# Schematic.net
KiCad netlist of a schematic drawn in EAGLE
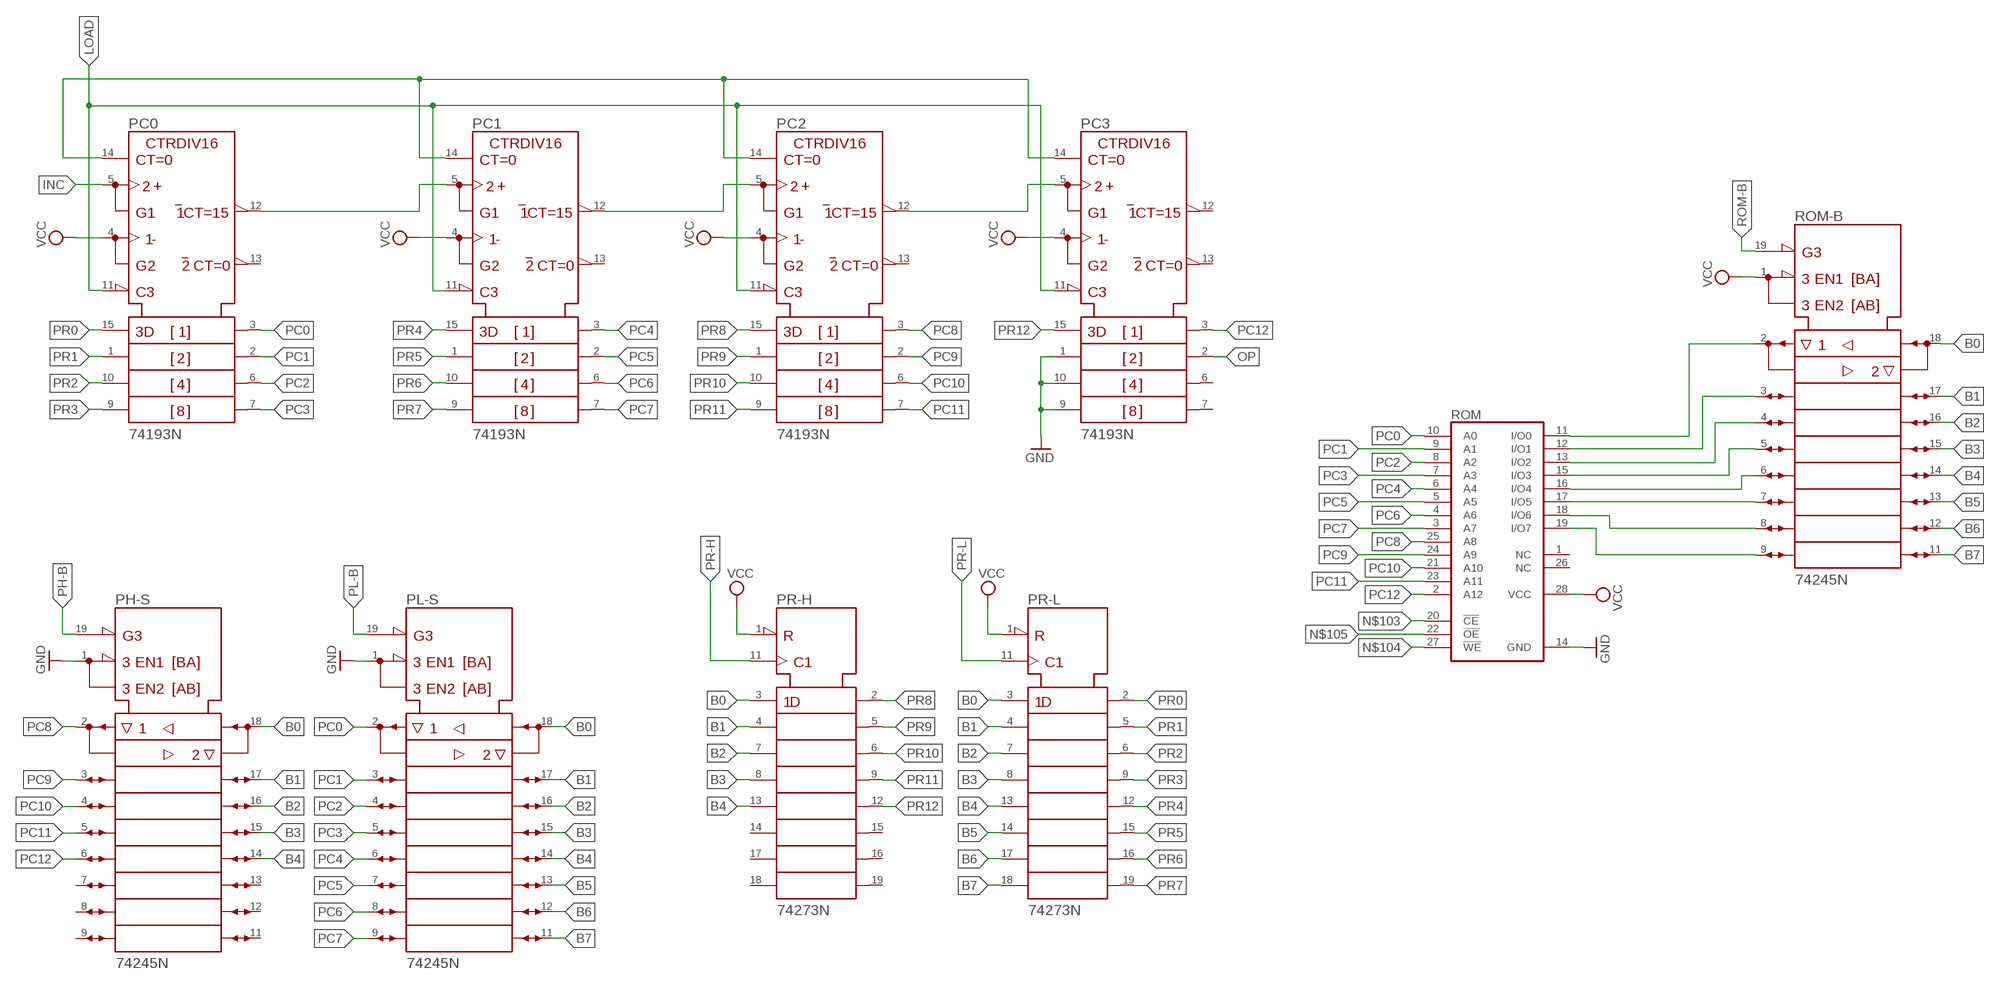
[diagram p0: schematic, sheet 1, part 1 of 3]
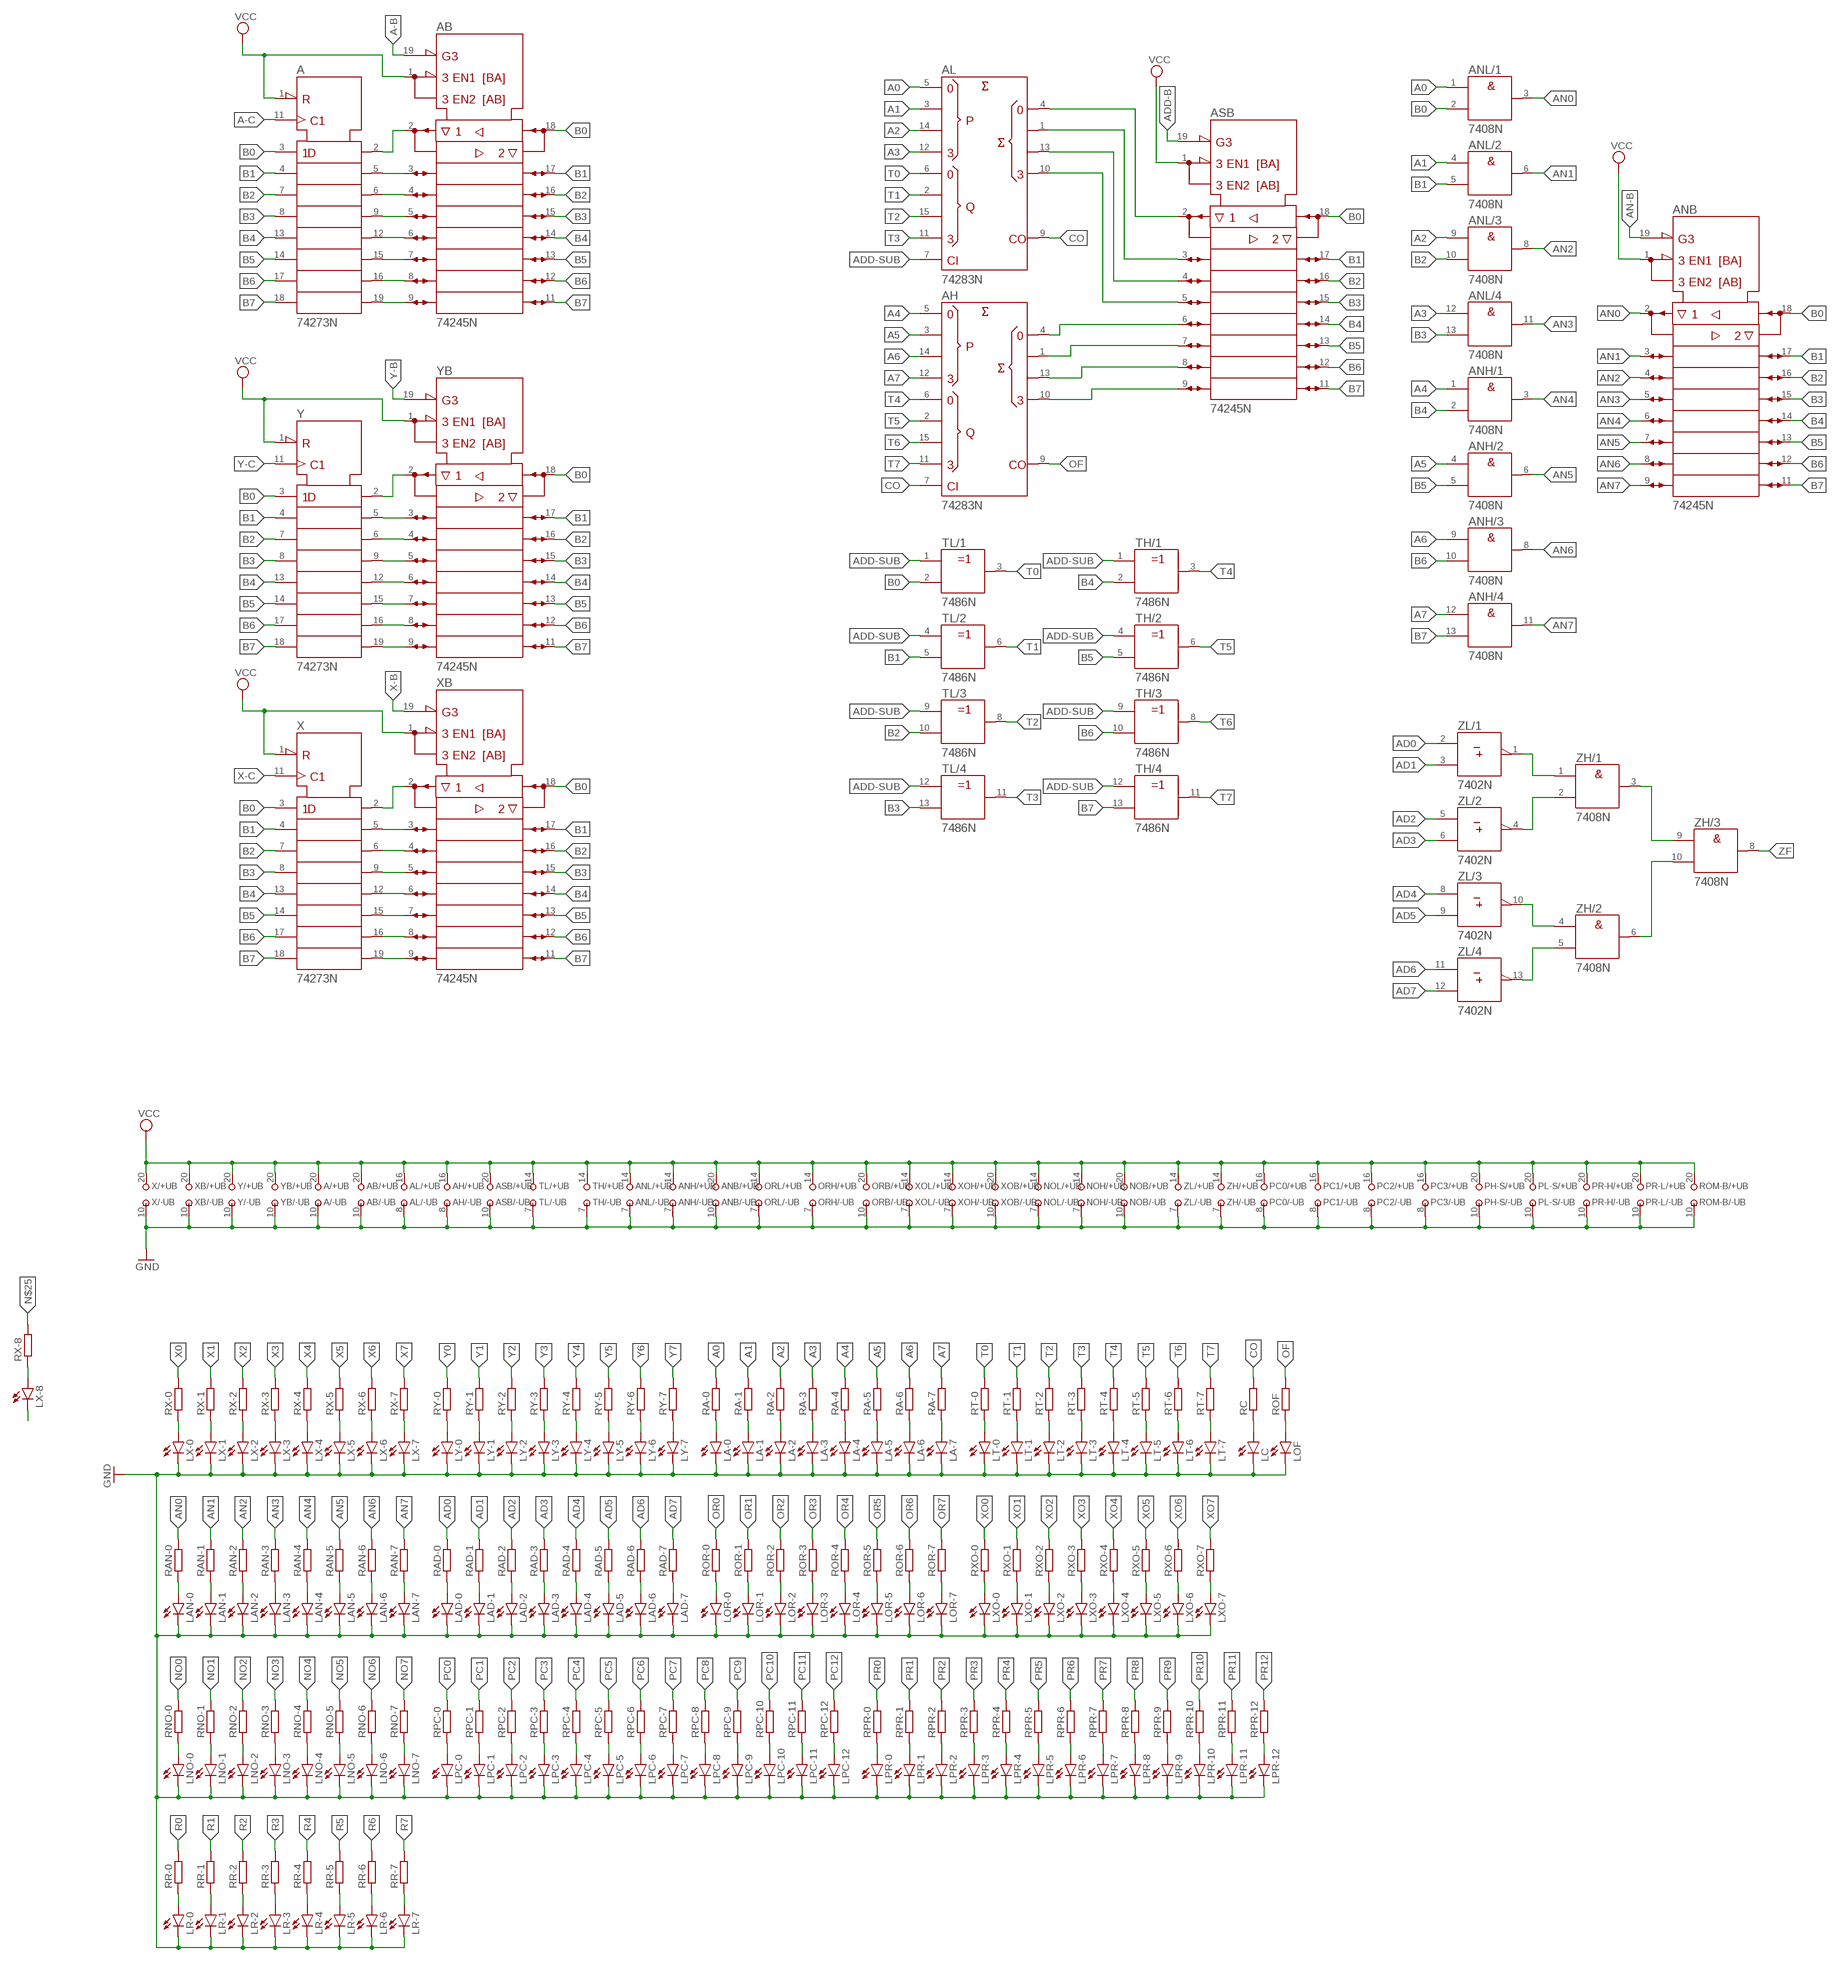
[diagram p1: schematic, sheet 1, part 2 of 3]
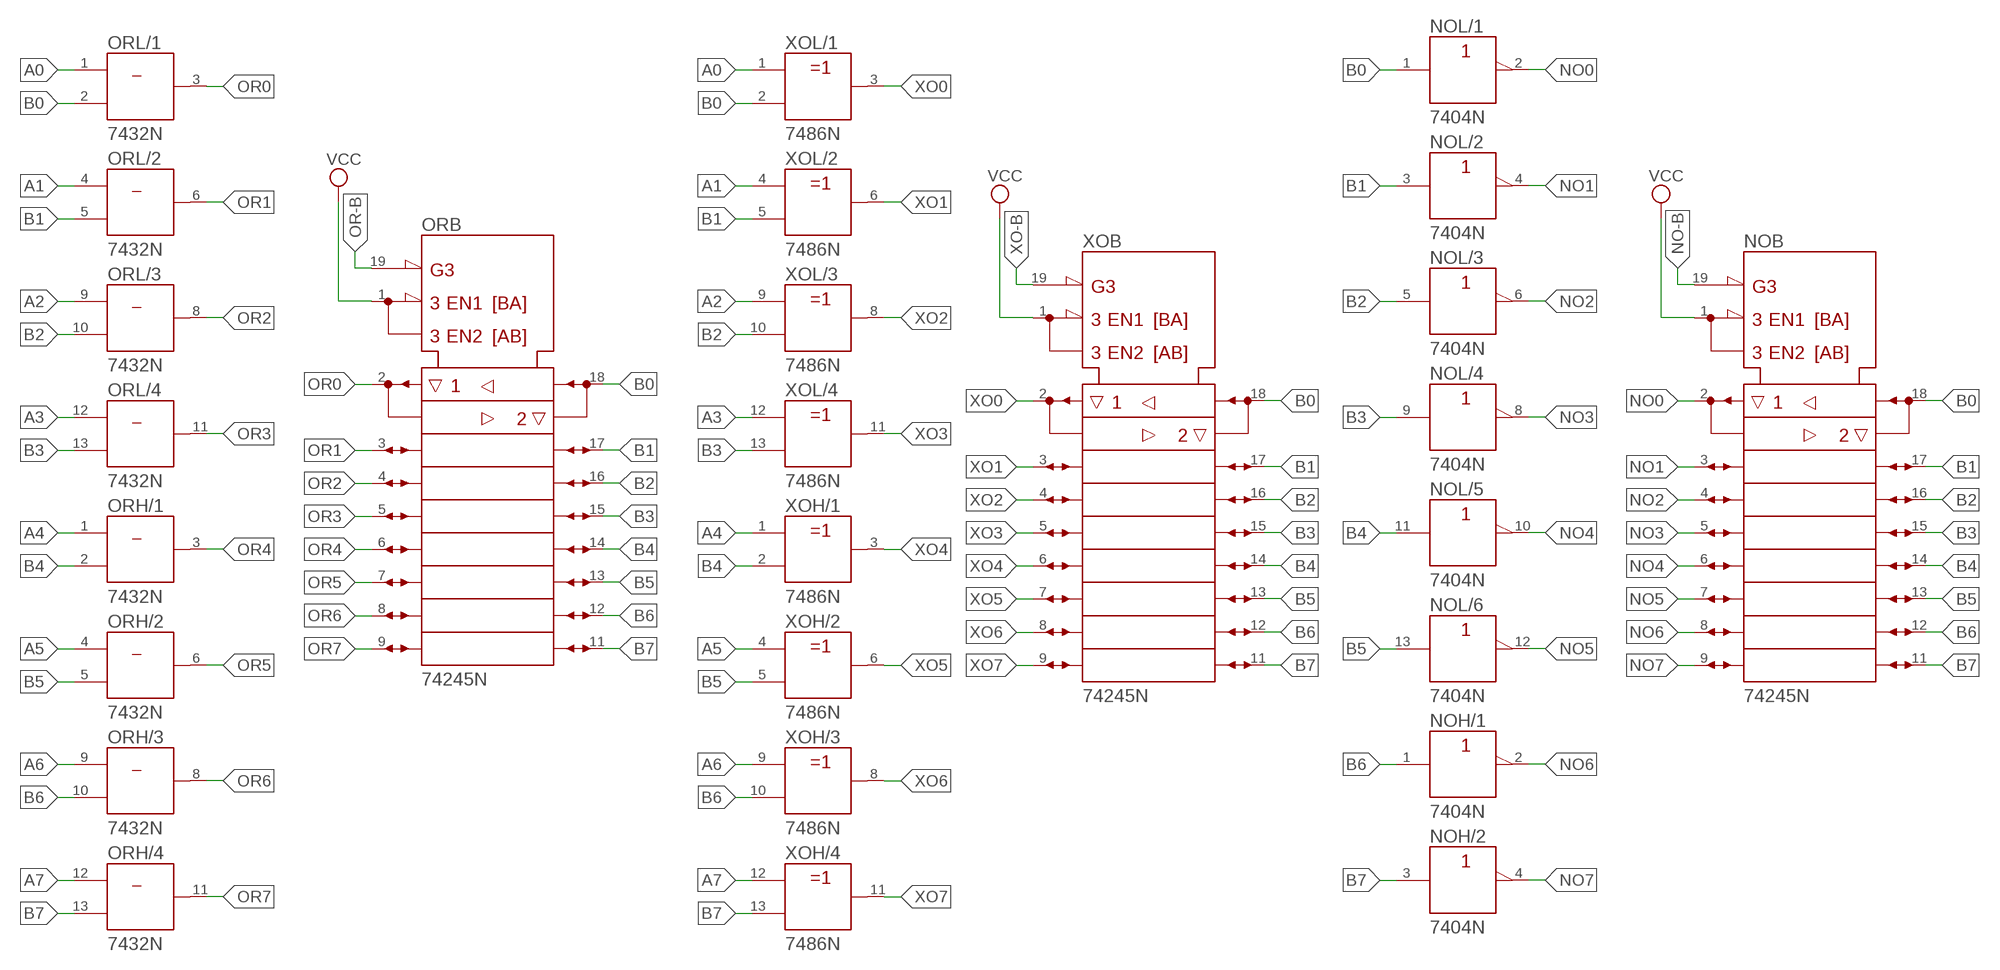
[diagram p2: schematic, sheet 1, part 3 of 3]

(export (version "E")
  (design (tool "Eeschema 10.0.6"))
  (components
    (comp (ref "A")
      (value "74273N")
      (footprint "eagle-import:DIL20")
      (libsource (lib "eagle-import") (part "74273N"))
    )
    (comp (ref "AB")
      (value "74245N")
      (footprint "eagle-import:DIL20")
      (libsource (lib "eagle-import") (part "74245N"))
    )
    (comp (ref "AH")
      (value "74283N")
      (footprint "eagle-import:DIL16")
      (libsource (lib "eagle-import") (part "74283N"))
    )
    (comp (ref "AL")
      (value "74283N")
      (footprint "eagle-import:DIL16")
      (libsource (lib "eagle-import") (part "74283N"))
    )
    (comp (ref "ANB")
      (value "74245N")
      (footprint "eagle-import:DIL20")
      (libsource (lib "eagle-import") (part "74245N"))
    )
    (comp (ref "ANH")
      (value "7408N")
      (footprint "eagle-import:DIL14")
      (libsource (lib "eagle-import") (part "7408N"))
    )
    (comp (ref "ANL")
      (value "7408N")
      (footprint "eagle-import:DIL14")
      (libsource (lib "eagle-import") (part "7408N"))
    )
    (comp (ref "ASB")
      (value "74245N")
      (footprint "eagle-import:DIL20")
      (libsource (lib "eagle-import") (part "74245N"))
    )
    (comp (ref "LA-0")
      (value "LED5MM")
      (footprint "eagle-import:LED5MM")
      (libsource (lib "eagle-import") (part "LED5MM"))
    )
    (comp (ref "LA-1")
      (value "LED5MM")
      (footprint "eagle-import:LED5MM")
      (libsource (lib "eagle-import") (part "LED5MM"))
    )
    (comp (ref "LA-2")
      (value "LED5MM")
      (footprint "eagle-import:LED5MM")
      (libsource (lib "eagle-import") (part "LED5MM"))
    )
    (comp (ref "LA-3")
      (value "LED5MM")
      (footprint "eagle-import:LED5MM")
      (libsource (lib "eagle-import") (part "LED5MM"))
    )
    (comp (ref "LA-4")
      (value "LED5MM")
      (footprint "eagle-import:LED5MM")
      (libsource (lib "eagle-import") (part "LED5MM"))
    )
    (comp (ref "LA-5")
      (value "LED5MM")
      (footprint "eagle-import:LED5MM")
      (libsource (lib "eagle-import") (part "LED5MM"))
    )
    (comp (ref "LA-6")
      (value "LED5MM")
      (footprint "eagle-import:LED5MM")
      (libsource (lib "eagle-import") (part "LED5MM"))
    )
    (comp (ref "LA-7")
      (value "LED5MM")
      (footprint "eagle-import:LED5MM")
      (libsource (lib "eagle-import") (part "LED5MM"))
    )
    (comp (ref "LAD-0")
      (value "LED5MM")
      (footprint "eagle-import:LED5MM")
      (libsource (lib "eagle-import") (part "LED5MM"))
    )
    (comp (ref "LAD-1")
      (value "LED5MM")
      (footprint "eagle-import:LED5MM")
      (libsource (lib "eagle-import") (part "LED5MM"))
    )
    (comp (ref "LAD-2")
      (value "LED5MM")
      (footprint "eagle-import:LED5MM")
      (libsource (lib "eagle-import") (part "LED5MM"))
    )
    (comp (ref "LAD-3")
      (value "LED5MM")
      (footprint "eagle-import:LED5MM")
      (libsource (lib "eagle-import") (part "LED5MM"))
    )
    (comp (ref "LAD-4")
      (value "LED5MM")
      (footprint "eagle-import:LED5MM")
      (libsource (lib "eagle-import") (part "LED5MM"))
    )
    (comp (ref "LAD-5")
      (value "LED5MM")
      (footprint "eagle-import:LED5MM")
      (libsource (lib "eagle-import") (part "LED5MM"))
    )
    (comp (ref "LAD-6")
      (value "LED5MM")
      (footprint "eagle-import:LED5MM")
      (libsource (lib "eagle-import") (part "LED5MM"))
    )
    (comp (ref "LAD-7")
      (value "LED5MM")
      (footprint "eagle-import:LED5MM")
      (libsource (lib "eagle-import") (part "LED5MM"))
    )
    (comp (ref "LAN-0")
      (value "LED5MM")
      (footprint "eagle-import:LED5MM")
      (libsource (lib "eagle-import") (part "LED5MM"))
    )
    (comp (ref "LAN-1")
      (value "LED5MM")
      (footprint "eagle-import:LED5MM")
      (libsource (lib "eagle-import") (part "LED5MM"))
    )
    (comp (ref "LAN-2")
      (value "LED5MM")
      (footprint "eagle-import:LED5MM")
      (libsource (lib "eagle-import") (part "LED5MM"))
    )
    (comp (ref "LAN-3")
      (value "LED5MM")
      (footprint "eagle-import:LED5MM")
      (libsource (lib "eagle-import") (part "LED5MM"))
    )
    (comp (ref "LAN-4")
      (value "LED5MM")
      (footprint "eagle-import:LED5MM")
      (libsource (lib "eagle-import") (part "LED5MM"))
    )
    (comp (ref "LAN-5")
      (value "LED5MM")
      (footprint "eagle-import:LED5MM")
      (libsource (lib "eagle-import") (part "LED5MM"))
    )
    (comp (ref "LAN-6")
      (value "LED5MM")
      (footprint "eagle-import:LED5MM")
      (libsource (lib "eagle-import") (part "LED5MM"))
    )
    (comp (ref "LAN-7")
      (value "LED5MM")
      (footprint "eagle-import:LED5MM")
      (libsource (lib "eagle-import") (part "LED5MM"))
    )
    (comp (ref "LC")
      (value "LED5MM")
      (footprint "eagle-import:LED5MM")
      (libsource (lib "eagle-import") (part "LED5MM"))
    )
    (comp (ref "LNO-0")
      (value "LED5MM")
      (footprint "eagle-import:LED5MM")
      (libsource (lib "eagle-import") (part "LED5MM"))
    )
    (comp (ref "LNO-1")
      (value "LED5MM")
      (footprint "eagle-import:LED5MM")
      (libsource (lib "eagle-import") (part "LED5MM"))
    )
    (comp (ref "LNO-2")
      (value "LED5MM")
      (footprint "eagle-import:LED5MM")
      (libsource (lib "eagle-import") (part "LED5MM"))
    )
    (comp (ref "LNO-3")
      (value "LED5MM")
      (footprint "eagle-import:LED5MM")
      (libsource (lib "eagle-import") (part "LED5MM"))
    )
    (comp (ref "LNO-4")
      (value "LED5MM")
      (footprint "eagle-import:LED5MM")
      (libsource (lib "eagle-import") (part "LED5MM"))
    )
    (comp (ref "LNO-5")
      (value "LED5MM")
      (footprint "eagle-import:LED5MM")
      (libsource (lib "eagle-import") (part "LED5MM"))
    )
    (comp (ref "LNO-6")
      (value "LED5MM")
      (footprint "eagle-import:LED5MM")
      (libsource (lib "eagle-import") (part "LED5MM"))
    )
    (comp (ref "LNO-7")
      (value "LED5MM")
      (footprint "eagle-import:LED5MM")
      (libsource (lib "eagle-import") (part "LED5MM"))
    )
    (comp (ref "LOF")
      (value "LED5MM")
      (footprint "eagle-import:LED5MM")
      (libsource (lib "eagle-import") (part "LED5MM"))
    )
    (comp (ref "LOR-0")
      (value "LED5MM")
      (footprint "eagle-import:LED5MM")
      (libsource (lib "eagle-import") (part "LED5MM"))
    )
    (comp (ref "LOR-1")
      (value "LED5MM")
      (footprint "eagle-import:LED5MM")
      (libsource (lib "eagle-import") (part "LED5MM"))
    )
    (comp (ref "LOR-2")
      (value "LED5MM")
      (footprint "eagle-import:LED5MM")
      (libsource (lib "eagle-import") (part "LED5MM"))
    )
    (comp (ref "LOR-3")
      (value "LED5MM")
      (footprint "eagle-import:LED5MM")
      (libsource (lib "eagle-import") (part "LED5MM"))
    )
    (comp (ref "LOR-4")
      (value "LED5MM")
      (footprint "eagle-import:LED5MM")
      (libsource (lib "eagle-import") (part "LED5MM"))
    )
    (comp (ref "LOR-5")
      (value "LED5MM")
      (footprint "eagle-import:LED5MM")
      (libsource (lib "eagle-import") (part "LED5MM"))
    )
    (comp (ref "LOR-6")
      (value "LED5MM")
      (footprint "eagle-import:LED5MM")
      (libsource (lib "eagle-import") (part "LED5MM"))
    )
    (comp (ref "LOR-7")
      (value "LED5MM")
      (footprint "eagle-import:LED5MM")
      (libsource (lib "eagle-import") (part "LED5MM"))
    )
    (comp (ref "LPC-0")
      (value "LED5MM")
      (footprint "eagle-import:LED5MM")
      (libsource (lib "eagle-import") (part "LED5MM"))
    )
    (comp (ref "LPC-1")
      (value "LED5MM")
      (footprint "eagle-import:LED5MM")
      (libsource (lib "eagle-import") (part "LED5MM"))
    )
    (comp (ref "LPC-2")
      (value "LED5MM")
      (footprint "eagle-import:LED5MM")
      (libsource (lib "eagle-import") (part "LED5MM"))
    )
    (comp (ref "LPC-3")
      (value "LED5MM")
      (footprint "eagle-import:LED5MM")
      (libsource (lib "eagle-import") (part "LED5MM"))
    )
    (comp (ref "LPC-4")
      (value "LED5MM")
      (footprint "eagle-import:LED5MM")
      (libsource (lib "eagle-import") (part "LED5MM"))
    )
    (comp (ref "LPC-5")
      (value "LED5MM")
      (footprint "eagle-import:LED5MM")
      (libsource (lib "eagle-import") (part "LED5MM"))
    )
    (comp (ref "LPC-6")
      (value "LED5MM")
      (footprint "eagle-import:LED5MM")
      (libsource (lib "eagle-import") (part "LED5MM"))
    )
    (comp (ref "LPC-7")
      (value "LED5MM")
      (footprint "eagle-import:LED5MM")
      (libsource (lib "eagle-import") (part "LED5MM"))
    )
    (comp (ref "LPC-8")
      (value "LED5MM")
      (footprint "eagle-import:LED5MM")
      (libsource (lib "eagle-import") (part "LED5MM"))
    )
    (comp (ref "LPC-9")
      (value "LED5MM")
      (footprint "eagle-import:LED5MM")
      (libsource (lib "eagle-import") (part "LED5MM"))
    )
    (comp (ref "LPC-10")
      (value "LED5MM")
      (footprint "eagle-import:LED5MM")
      (libsource (lib "eagle-import") (part "LED5MM"))
    )
    (comp (ref "LPC-11")
      (value "LED5MM")
      (footprint "eagle-import:LED5MM")
      (libsource (lib "eagle-import") (part "LED5MM"))
    )
    (comp (ref "LPC-12")
      (value "LED5MM")
      (footprint "eagle-import:LED5MM")
      (libsource (lib "eagle-import") (part "LED5MM"))
    )
    (comp (ref "LPR-0")
      (value "LED5MM")
      (footprint "eagle-import:LED5MM")
      (libsource (lib "eagle-import") (part "LED5MM"))
    )
    (comp (ref "LPR-1")
      (value "LED5MM")
      (footprint "eagle-import:LED5MM")
      (libsource (lib "eagle-import") (part "LED5MM"))
    )
    (comp (ref "LPR-2")
      (value "LED5MM")
      (footprint "eagle-import:LED5MM")
      (libsource (lib "eagle-import") (part "LED5MM"))
    )
    (comp (ref "LPR-3")
      (value "LED5MM")
      (footprint "eagle-import:LED5MM")
      (libsource (lib "eagle-import") (part "LED5MM"))
    )
    (comp (ref "LPR-4")
      (value "LED5MM")
      (footprint "eagle-import:LED5MM")
      (libsource (lib "eagle-import") (part "LED5MM"))
    )
    (comp (ref "LPR-5")
      (value "LED5MM")
      (footprint "eagle-import:LED5MM")
      (libsource (lib "eagle-import") (part "LED5MM"))
    )
    (comp (ref "LPR-6")
      (value "LED5MM")
      (footprint "eagle-import:LED5MM")
      (libsource (lib "eagle-import") (part "LED5MM"))
    )
    (comp (ref "LPR-7")
      (value "LED5MM")
      (footprint "eagle-import:LED5MM")
      (libsource (lib "eagle-import") (part "LED5MM"))
    )
    (comp (ref "LPR-8")
      (value "LED5MM")
      (footprint "eagle-import:LED5MM")
      (libsource (lib "eagle-import") (part "LED5MM"))
    )
    (comp (ref "LPR-9")
      (value "LED5MM")
      (footprint "eagle-import:LED5MM")
      (libsource (lib "eagle-import") (part "LED5MM"))
    )
    (comp (ref "LPR-10")
      (value "LED5MM")
      (footprint "eagle-import:LED5MM")
      (libsource (lib "eagle-import") (part "LED5MM"))
    )
    (comp (ref "LPR-11")
      (value "LED5MM")
      (footprint "eagle-import:LED5MM")
      (libsource (lib "eagle-import") (part "LED5MM"))
    )
    (comp (ref "LPR-12")
      (value "LED5MM")
      (footprint "eagle-import:LED5MM")
      (libsource (lib "eagle-import") (part "LED5MM"))
    )
    (comp (ref "LR-0")
      (value "LED5MM")
      (footprint "eagle-import:LED5MM")
      (libsource (lib "eagle-import") (part "LED5MM"))
    )
    (comp (ref "LR-1")
      (value "LED5MM")
      (footprint "eagle-import:LED5MM")
      (libsource (lib "eagle-import") (part "LED5MM"))
    )
    (comp (ref "LR-2")
      (value "LED5MM")
      (footprint "eagle-import:LED5MM")
      (libsource (lib "eagle-import") (part "LED5MM"))
    )
    (comp (ref "LR-3")
      (value "LED5MM")
      (footprint "eagle-import:LED5MM")
      (libsource (lib "eagle-import") (part "LED5MM"))
    )
    (comp (ref "LR-4")
      (value "LED5MM")
      (footprint "eagle-import:LED5MM")
      (libsource (lib "eagle-import") (part "LED5MM"))
    )
    (comp (ref "LR-5")
      (value "LED5MM")
      (footprint "eagle-import:LED5MM")
      (libsource (lib "eagle-import") (part "LED5MM"))
    )
    (comp (ref "LR-6")
      (value "LED5MM")
      (footprint "eagle-import:LED5MM")
      (libsource (lib "eagle-import") (part "LED5MM"))
    )
    (comp (ref "LR-7")
      (value "LED5MM")
      (footprint "eagle-import:LED5MM")
      (libsource (lib "eagle-import") (part "LED5MM"))
    )
    (comp (ref "LT-0")
      (value "LED5MM")
      (footprint "eagle-import:LED5MM")
      (libsource (lib "eagle-import") (part "LED5MM"))
    )
    (comp (ref "LT-1")
      (value "LED5MM")
      (footprint "eagle-import:LED5MM")
      (libsource (lib "eagle-import") (part "LED5MM"))
    )
    (comp (ref "LT-2")
      (value "LED5MM")
      (footprint "eagle-import:LED5MM")
      (libsource (lib "eagle-import") (part "LED5MM"))
    )
    (comp (ref "LT-3")
      (value "LED5MM")
      (footprint "eagle-import:LED5MM")
      (libsource (lib "eagle-import") (part "LED5MM"))
    )
    (comp (ref "LT-4")
      (value "LED5MM")
      (footprint "eagle-import:LED5MM")
      (libsource (lib "eagle-import") (part "LED5MM"))
    )
    (comp (ref "LT-5")
      (value "LED5MM")
      (footprint "eagle-import:LED5MM")
      (libsource (lib "eagle-import") (part "LED5MM"))
    )
    (comp (ref "LT-6")
      (value "LED5MM")
      (footprint "eagle-import:LED5MM")
      (libsource (lib "eagle-import") (part "LED5MM"))
    )
    (comp (ref "LT-7")
      (value "LED5MM")
      (footprint "eagle-import:LED5MM")
      (libsource (lib "eagle-import") (part "LED5MM"))
    )
    (comp (ref "LX-0")
      (value "LED5MM")
      (footprint "eagle-import:LED5MM")
      (libsource (lib "eagle-import") (part "LED5MM"))
    )
    (comp (ref "LX-1")
      (value "LED5MM")
      (footprint "eagle-import:LED5MM")
      (libsource (lib "eagle-import") (part "LED5MM"))
    )
    (comp (ref "LX-2")
      (value "LED5MM")
      (footprint "eagle-import:LED5MM")
      (libsource (lib "eagle-import") (part "LED5MM"))
    )
    (comp (ref "LX-3")
      (value "LED5MM")
      (footprint "eagle-import:LED5MM")
      (libsource (lib "eagle-import") (part "LED5MM"))
    )
    (comp (ref "LX-4")
      (value "LED5MM")
      (footprint "eagle-import:LED5MM")
      (libsource (lib "eagle-import") (part "LED5MM"))
    )
    (comp (ref "LX-5")
      (value "LED5MM")
      (footprint "eagle-import:LED5MM")
      (libsource (lib "eagle-import") (part "LED5MM"))
    )
    (comp (ref "LX-6")
      (value "LED5MM")
      (footprint "eagle-import:LED5MM")
      (libsource (lib "eagle-import") (part "LED5MM"))
    )
    (comp (ref "LX-7")
      (value "LED5MM")
      (footprint "eagle-import:LED5MM")
      (libsource (lib "eagle-import") (part "LED5MM"))
    )
    (comp (ref "LX-8")
      (value "LED5MM")
      (footprint "eagle-import:LED5MM")
      (libsource (lib "eagle-import") (part "LED5MM"))
    )
    (comp (ref "LXO-0")
      (value "LED5MM")
      (footprint "eagle-import:LED5MM")
      (libsource (lib "eagle-import") (part "LED5MM"))
    )
    (comp (ref "LXO-1")
      (value "LED5MM")
      (footprint "eagle-import:LED5MM")
      (libsource (lib "eagle-import") (part "LED5MM"))
    )
    (comp (ref "LXO-2")
      (value "LED5MM")
      (footprint "eagle-import:LED5MM")
      (libsource (lib "eagle-import") (part "LED5MM"))
    )
    (comp (ref "LXO-3")
      (value "LED5MM")
      (footprint "eagle-import:LED5MM")
      (libsource (lib "eagle-import") (part "LED5MM"))
    )
    (comp (ref "LXO-4")
      (value "LED5MM")
      (footprint "eagle-import:LED5MM")
      (libsource (lib "eagle-import") (part "LED5MM"))
    )
    (comp (ref "LXO-5")
      (value "LED5MM")
      (footprint "eagle-import:LED5MM")
      (libsource (lib "eagle-import") (part "LED5MM"))
    )
    (comp (ref "LXO-6")
      (value "LED5MM")
      (footprint "eagle-import:LED5MM")
      (libsource (lib "eagle-import") (part "LED5MM"))
    )
    (comp (ref "LXO-7")
      (value "LED5MM")
      (footprint "eagle-import:LED5MM")
      (libsource (lib "eagle-import") (part "LED5MM"))
    )
    (comp (ref "LY-0")
      (value "LED5MM")
      (footprint "eagle-import:LED5MM")
      (libsource (lib "eagle-import") (part "LED5MM"))
    )
    (comp (ref "LY-1")
      (value "LED5MM")
      (footprint "eagle-import:LED5MM")
      (libsource (lib "eagle-import") (part "LED5MM"))
    )
    (comp (ref "LY-2")
      (value "LED5MM")
      (footprint "eagle-import:LED5MM")
      (libsource (lib "eagle-import") (part "LED5MM"))
    )
    (comp (ref "LY-3")
      (value "LED5MM")
      (footprint "eagle-import:LED5MM")
      (libsource (lib "eagle-import") (part "LED5MM"))
    )
    (comp (ref "LY-4")
      (value "LED5MM")
      (footprint "eagle-import:LED5MM")
      (libsource (lib "eagle-import") (part "LED5MM"))
    )
    (comp (ref "LY-5")
      (value "LED5MM")
      (footprint "eagle-import:LED5MM")
      (libsource (lib "eagle-import") (part "LED5MM"))
    )
    (comp (ref "LY-6")
      (value "LED5MM")
      (footprint "eagle-import:LED5MM")
      (libsource (lib "eagle-import") (part "LED5MM"))
    )
    (comp (ref "LY-7")
      (value "LED5MM")
      (footprint "eagle-import:LED5MM")
      (libsource (lib "eagle-import") (part "LED5MM"))
    )
    (comp (ref "NOB")
      (value "74245N")
      (footprint "eagle-import:DIL20")
      (libsource (lib "eagle-import") (part "74245N"))
    )
    (comp (ref "NOH")
      (value "7404N")
      (footprint "eagle-import:DIL14")
      (libsource (lib "eagle-import") (part "7404N"))
    )
    (comp (ref "NOL")
      (value "7404N")
      (footprint "eagle-import:DIL14")
      (libsource (lib "eagle-import") (part "7404N"))
    )
    (comp (ref "ORB")
      (value "74245N")
      (footprint "eagle-import:DIL20")
      (libsource (lib "eagle-import") (part "74245N"))
    )
    (comp (ref "ORH")
      (value "7432N")
      (footprint "eagle-import:DIL14")
      (libsource (lib "eagle-import") (part "7432N"))
    )
    (comp (ref "ORL")
      (value "7432N")
      (footprint "eagle-import:DIL14")
      (libsource (lib "eagle-import") (part "7432N"))
    )
    (comp (ref "PC0")
      (value "74193N")
      (footprint "eagle-import:DIL16")
      (libsource (lib "eagle-import") (part "74193N"))
    )
    (comp (ref "PC1")
      (value "74193N")
      (footprint "eagle-import:DIL16")
      (libsource (lib "eagle-import") (part "74193N"))
    )
    (comp (ref "PC2")
      (value "74193N")
      (footprint "eagle-import:DIL16")
      (libsource (lib "eagle-import") (part "74193N"))
    )
    (comp (ref "PC3")
      (value "74193N")
      (footprint "eagle-import:DIL16")
      (libsource (lib "eagle-import") (part "74193N"))
    )
    (comp (ref "PH-S")
      (value "74245N")
      (footprint "eagle-import:DIL20")
      (libsource (lib "eagle-import") (part "74245N"))
    )
    (comp (ref "PL-S")
      (value "74245N")
      (footprint "eagle-import:DIL20")
      (libsource (lib "eagle-import") (part "74245N"))
    )
    (comp (ref "PR-H")
      (value "74273N")
      (footprint "eagle-import:DIL20")
      (libsource (lib "eagle-import") (part "74273N"))
    )
    (comp (ref "PR-L")
      (value "74273N")
      (footprint "eagle-import:DIL20")
      (libsource (lib "eagle-import") (part "74273N"))
    )
    (comp (ref "RA-0")
      (value "R-EU_0207/10")
      (footprint "eagle-import:0207_10")
      (libsource (lib "eagle-import") (part "R-EU_0207/10"))
    )
    (comp (ref "RA-1")
      (value "R-EU_0207/10")
      (footprint "eagle-import:0207_10")
      (libsource (lib "eagle-import") (part "R-EU_0207/10"))
    )
    (comp (ref "RA-2")
      (value "R-EU_0207/10")
      (footprint "eagle-import:0207_10")
      (libsource (lib "eagle-import") (part "R-EU_0207/10"))
    )
    (comp (ref "RA-3")
      (value "R-EU_0207/10")
      (footprint "eagle-import:0207_10")
      (libsource (lib "eagle-import") (part "R-EU_0207/10"))
    )
    (comp (ref "RA-4")
      (value "R-EU_0207/10")
      (footprint "eagle-import:0207_10")
      (libsource (lib "eagle-import") (part "R-EU_0207/10"))
    )
    (comp (ref "RA-5")
      (value "R-EU_0207/10")
      (footprint "eagle-import:0207_10")
      (libsource (lib "eagle-import") (part "R-EU_0207/10"))
    )
    (comp (ref "RA-6")
      (value "R-EU_0207/10")
      (footprint "eagle-import:0207_10")
      (libsource (lib "eagle-import") (part "R-EU_0207/10"))
    )
    (comp (ref "RA-7")
      (value "R-EU_0207/10")
      (footprint "eagle-import:0207_10")
      (libsource (lib "eagle-import") (part "R-EU_0207/10"))
    )
    (comp (ref "RAD-0")
      (value "R-EU_0207/10")
      (footprint "eagle-import:0207_10")
      (libsource (lib "eagle-import") (part "R-EU_0207/10"))
    )
    (comp (ref "RAD-1")
      (value "R-EU_0207/10")
      (footprint "eagle-import:0207_10")
      (libsource (lib "eagle-import") (part "R-EU_0207/10"))
    )
    (comp (ref "RAD-2")
      (value "R-EU_0207/10")
      (footprint "eagle-import:0207_10")
      (libsource (lib "eagle-import") (part "R-EU_0207/10"))
    )
    (comp (ref "RAD-3")
      (value "R-EU_0207/10")
      (footprint "eagle-import:0207_10")
      (libsource (lib "eagle-import") (part "R-EU_0207/10"))
    )
    (comp (ref "RAD-4")
      (value "R-EU_0207/10")
      (footprint "eagle-import:0207_10")
      (libsource (lib "eagle-import") (part "R-EU_0207/10"))
    )
    (comp (ref "RAD-5")
      (value "R-EU_0207/10")
      (footprint "eagle-import:0207_10")
      (libsource (lib "eagle-import") (part "R-EU_0207/10"))
    )
    (comp (ref "RAD-6")
      (value "R-EU_0207/10")
      (footprint "eagle-import:0207_10")
      (libsource (lib "eagle-import") (part "R-EU_0207/10"))
    )
    (comp (ref "RAD-7")
      (value "R-EU_0207/10")
      (footprint "eagle-import:0207_10")
      (libsource (lib "eagle-import") (part "R-EU_0207/10"))
    )
    (comp (ref "RAN-0")
      (value "R-EU_0207/10")
      (footprint "eagle-import:0207_10")
      (libsource (lib "eagle-import") (part "R-EU_0207/10"))
    )
    (comp (ref "RAN-1")
      (value "R-EU_0207/10")
      (footprint "eagle-import:0207_10")
      (libsource (lib "eagle-import") (part "R-EU_0207/10"))
    )
    (comp (ref "RAN-2")
      (value "R-EU_0207/10")
      (footprint "eagle-import:0207_10")
      (libsource (lib "eagle-import") (part "R-EU_0207/10"))
    )
    (comp (ref "RAN-3")
      (value "R-EU_0207/10")
      (footprint "eagle-import:0207_10")
      (libsource (lib "eagle-import") (part "R-EU_0207/10"))
    )
    (comp (ref "RAN-4")
      (value "R-EU_0207/10")
      (footprint "eagle-import:0207_10")
      (libsource (lib "eagle-import") (part "R-EU_0207/10"))
    )
    (comp (ref "RAN-5")
      (value "R-EU_0207/10")
      (footprint "eagle-import:0207_10")
      (libsource (lib "eagle-import") (part "R-EU_0207/10"))
    )
    (comp (ref "RAN-6")
      (value "R-EU_0207/10")
      (footprint "eagle-import:0207_10")
      (libsource (lib "eagle-import") (part "R-EU_0207/10"))
    )
    (comp (ref "RAN-7")
      (value "R-EU_0207/10")
      (footprint "eagle-import:0207_10")
      (libsource (lib "eagle-import") (part "R-EU_0207/10"))
    )
    (comp (ref "RC")
      (value "R-EU_0207/10")
      (footprint "eagle-import:0207_10")
      (libsource (lib "eagle-import") (part "R-EU_0207/10"))
    )
    (comp (ref "RNO-0")
      (value "R-EU_0207/10")
      (footprint "eagle-import:0207_10")
      (libsource (lib "eagle-import") (part "R-EU_0207/10"))
    )
    (comp (ref "RNO-1")
      (value "R-EU_0207/10")
      (footprint "eagle-import:0207_10")
      (libsource (lib "eagle-import") (part "R-EU_0207/10"))
    )
    (comp (ref "RNO-2")
      (value "R-EU_0207/10")
      (footprint "eagle-import:0207_10")
      (libsource (lib "eagle-import") (part "R-EU_0207/10"))
    )
    (comp (ref "RNO-3")
      (value "R-EU_0207/10")
      (footprint "eagle-import:0207_10")
      (libsource (lib "eagle-import") (part "R-EU_0207/10"))
    )
    (comp (ref "RNO-4")
      (value "R-EU_0207/10")
      (footprint "eagle-import:0207_10")
      (libsource (lib "eagle-import") (part "R-EU_0207/10"))
    )
    (comp (ref "RNO-5")
      (value "R-EU_0207/10")
      (footprint "eagle-import:0207_10")
      (libsource (lib "eagle-import") (part "R-EU_0207/10"))
    )
    (comp (ref "RNO-6")
      (value "R-EU_0207/10")
      (footprint "eagle-import:0207_10")
      (libsource (lib "eagle-import") (part "R-EU_0207/10"))
    )
    (comp (ref "RNO-7")
      (value "R-EU_0207/10")
      (footprint "eagle-import:0207_10")
      (libsource (lib "eagle-import") (part "R-EU_0207/10"))
    )
    (comp (ref "ROF")
      (value "R-EU_0207/10")
      (footprint "eagle-import:0207_10")
      (libsource (lib "eagle-import") (part "R-EU_0207/10"))
    )
    (comp (ref "ROM")
      (value "28C64C")
      (footprint "eagle-import:DIL28-6")
      (fields (field (name "MPN") "AT28C64B-15PU"))
      (libsource (lib "eagle-import") (part "28C64C"))
    )
    (comp (ref "ROM-B")
      (value "74245N")
      (footprint "eagle-import:DIL20")
      (libsource (lib "eagle-import") (part "74245N"))
    )
    (comp (ref "ROR-0")
      (value "R-EU_0207/10")
      (footprint "eagle-import:0207_10")
      (libsource (lib "eagle-import") (part "R-EU_0207/10"))
    )
    (comp (ref "ROR-1")
      (value "R-EU_0207/10")
      (footprint "eagle-import:0207_10")
      (libsource (lib "eagle-import") (part "R-EU_0207/10"))
    )
    (comp (ref "ROR-2")
      (value "R-EU_0207/10")
      (footprint "eagle-import:0207_10")
      (libsource (lib "eagle-import") (part "R-EU_0207/10"))
    )
    (comp (ref "ROR-3")
      (value "R-EU_0207/10")
      (footprint "eagle-import:0207_10")
      (libsource (lib "eagle-import") (part "R-EU_0207/10"))
    )
    (comp (ref "ROR-4")
      (value "R-EU_0207/10")
      (footprint "eagle-import:0207_10")
      (libsource (lib "eagle-import") (part "R-EU_0207/10"))
    )
    (comp (ref "ROR-5")
      (value "R-EU_0207/10")
      (footprint "eagle-import:0207_10")
      (libsource (lib "eagle-import") (part "R-EU_0207/10"))
    )
    (comp (ref "ROR-6")
      (value "R-EU_0207/10")
      (footprint "eagle-import:0207_10")
      (libsource (lib "eagle-import") (part "R-EU_0207/10"))
    )
    (comp (ref "ROR-7")
      (value "R-EU_0207/10")
      (footprint "eagle-import:0207_10")
      (libsource (lib "eagle-import") (part "R-EU_0207/10"))
    )
    (comp (ref "RPC-0")
      (value "R-EU_0207/10")
      (footprint "eagle-import:0207_10")
      (libsource (lib "eagle-import") (part "R-EU_0207/10"))
    )
    (comp (ref "RPC-1")
      (value "R-EU_0207/10")
      (footprint "eagle-import:0207_10")
      (libsource (lib "eagle-import") (part "R-EU_0207/10"))
    )
    (comp (ref "RPC-2")
      (value "R-EU_0207/10")
      (footprint "eagle-import:0207_10")
      (libsource (lib "eagle-import") (part "R-EU_0207/10"))
    )
    (comp (ref "RPC-3")
      (value "R-EU_0207/10")
      (footprint "eagle-import:0207_10")
      (libsource (lib "eagle-import") (part "R-EU_0207/10"))
    )
    (comp (ref "RPC-4")
      (value "R-EU_0207/10")
      (footprint "eagle-import:0207_10")
      (libsource (lib "eagle-import") (part "R-EU_0207/10"))
    )
    (comp (ref "RPC-5")
      (value "R-EU_0207/10")
      (footprint "eagle-import:0207_10")
      (libsource (lib "eagle-import") (part "R-EU_0207/10"))
    )
    (comp (ref "RPC-6")
      (value "R-EU_0207/10")
      (footprint "eagle-import:0207_10")
      (libsource (lib "eagle-import") (part "R-EU_0207/10"))
    )
    (comp (ref "RPC-7")
      (value "R-EU_0207/10")
      (footprint "eagle-import:0207_10")
      (libsource (lib "eagle-import") (part "R-EU_0207/10"))
    )
    (comp (ref "RPC-8")
      (value "R-EU_0207/10")
      (footprint "eagle-import:0207_10")
      (libsource (lib "eagle-import") (part "R-EU_0207/10"))
    )
    (comp (ref "RPC-9")
      (value "R-EU_0207/10")
      (footprint "eagle-import:0207_10")
      (libsource (lib "eagle-import") (part "R-EU_0207/10"))
    )
    (comp (ref "RPC-10")
      (value "R-EU_0207/10")
      (footprint "eagle-import:0207_10")
      (libsource (lib "eagle-import") (part "R-EU_0207/10"))
    )
    (comp (ref "RPC-11")
      (value "R-EU_0207/10")
      (footprint "eagle-import:0207_10")
      (libsource (lib "eagle-import") (part "R-EU_0207/10"))
    )
    (comp (ref "RPC-12")
      (value "R-EU_0207/10")
      (footprint "eagle-import:0207_10")
      (libsource (lib "eagle-import") (part "R-EU_0207/10"))
    )
    (comp (ref "RPR-0")
      (value "R-EU_0207/10")
      (footprint "eagle-import:0207_10")
      (libsource (lib "eagle-import") (part "R-EU_0207/10"))
    )
    (comp (ref "RPR-1")
      (value "R-EU_0207/10")
      (footprint "eagle-import:0207_10")
      (libsource (lib "eagle-import") (part "R-EU_0207/10"))
    )
    (comp (ref "RPR-2")
      (value "R-EU_0207/10")
      (footprint "eagle-import:0207_10")
      (libsource (lib "eagle-import") (part "R-EU_0207/10"))
    )
    (comp (ref "RPR-3")
      (value "R-EU_0207/10")
      (footprint "eagle-import:0207_10")
      (libsource (lib "eagle-import") (part "R-EU_0207/10"))
    )
    (comp (ref "RPR-4")
      (value "R-EU_0207/10")
      (footprint "eagle-import:0207_10")
      (libsource (lib "eagle-import") (part "R-EU_0207/10"))
    )
    (comp (ref "RPR-5")
      (value "R-EU_0207/10")
      (footprint "eagle-import:0207_10")
      (libsource (lib "eagle-import") (part "R-EU_0207/10"))
    )
    (comp (ref "RPR-6")
      (value "R-EU_0207/10")
      (footprint "eagle-import:0207_10")
      (libsource (lib "eagle-import") (part "R-EU_0207/10"))
    )
    (comp (ref "RPR-7")
      (value "R-EU_0207/10")
      (footprint "eagle-import:0207_10")
      (libsource (lib "eagle-import") (part "R-EU_0207/10"))
    )
    (comp (ref "RPR-8")
      (value "R-EU_0207/10")
      (footprint "eagle-import:0207_10")
      (libsource (lib "eagle-import") (part "R-EU_0207/10"))
    )
    (comp (ref "RPR-9")
      (value "R-EU_0207/10")
      (footprint "eagle-import:0207_10")
      (libsource (lib "eagle-import") (part "R-EU_0207/10"))
    )
    (comp (ref "RPR-10")
      (value "R-EU_0207/10")
      (footprint "eagle-import:0207_10")
      (libsource (lib "eagle-import") (part "R-EU_0207/10"))
    )
    (comp (ref "RPR-11")
      (value "R-EU_0207/10")
      (footprint "eagle-import:0207_10")
      (libsource (lib "eagle-import") (part "R-EU_0207/10"))
    )
    (comp (ref "RPR-12")
      (value "R-EU_0207/10")
      (footprint "eagle-import:0207_10")
      (libsource (lib "eagle-import") (part "R-EU_0207/10"))
    )
    (comp (ref "RR-0")
      (value "R-EU_0207/10")
      (footprint "eagle-import:0207_10")
      (libsource (lib "eagle-import") (part "R-EU_0207/10"))
    )
    (comp (ref "RR-1")
      (value "R-EU_0207/10")
      (footprint "eagle-import:0207_10")
      (libsource (lib "eagle-import") (part "R-EU_0207/10"))
    )
    (comp (ref "RR-2")
      (value "R-EU_0207/10")
      (footprint "eagle-import:0207_10")
      (libsource (lib "eagle-import") (part "R-EU_0207/10"))
    )
    (comp (ref "RR-3")
      (value "R-EU_0207/10")
      (footprint "eagle-import:0207_10")
      (libsource (lib "eagle-import") (part "R-EU_0207/10"))
    )
    (comp (ref "RR-4")
      (value "R-EU_0207/10")
      (footprint "eagle-import:0207_10")
      (libsource (lib "eagle-import") (part "R-EU_0207/10"))
    )
    (comp (ref "RR-5")
      (value "R-EU_0207/10")
      (footprint "eagle-import:0207_10")
      (libsource (lib "eagle-import") (part "R-EU_0207/10"))
    )
    (comp (ref "RR-6")
      (value "R-EU_0207/10")
      (footprint "eagle-import:0207_10")
      (libsource (lib "eagle-import") (part "R-EU_0207/10"))
    )
    (comp (ref "RR-7")
      (value "R-EU_0207/10")
      (footprint "eagle-import:0207_10")
      (libsource (lib "eagle-import") (part "R-EU_0207/10"))
    )
    (comp (ref "RT-0")
      (value "R-EU_0207/10")
      (footprint "eagle-import:0207_10")
      (libsource (lib "eagle-import") (part "R-EU_0207/10"))
    )
    (comp (ref "RT-1")
      (value "R-EU_0207/10")
      (footprint "eagle-import:0207_10")
      (libsource (lib "eagle-import") (part "R-EU_0207/10"))
    )
    (comp (ref "RT-2")
      (value "R-EU_0207/10")
      (footprint "eagle-import:0207_10")
      (libsource (lib "eagle-import") (part "R-EU_0207/10"))
    )
    (comp (ref "RT-3")
      (value "R-EU_0207/10")
      (footprint "eagle-import:0207_10")
      (libsource (lib "eagle-import") (part "R-EU_0207/10"))
    )
    (comp (ref "RT-4")
      (value "R-EU_0207/10")
      (footprint "eagle-import:0207_10")
      (libsource (lib "eagle-import") (part "R-EU_0207/10"))
    )
    (comp (ref "RT-5")
      (value "R-EU_0207/10")
      (footprint "eagle-import:0207_10")
      (libsource (lib "eagle-import") (part "R-EU_0207/10"))
    )
    (comp (ref "RT-6")
      (value "R-EU_0207/10")
      (footprint "eagle-import:0207_10")
      (libsource (lib "eagle-import") (part "R-EU_0207/10"))
    )
    (comp (ref "RT-7")
      (value "R-EU_0207/10")
      (footprint "eagle-import:0207_10")
      (libsource (lib "eagle-import") (part "R-EU_0207/10"))
    )
    (comp (ref "RX-0")
      (value "R-EU_0207/10")
      (footprint "eagle-import:0207_10")
      (libsource (lib "eagle-import") (part "R-EU_0207/10"))
    )
    (comp (ref "RX-1")
      (value "R-EU_0207/10")
      (footprint "eagle-import:0207_10")
      (libsource (lib "eagle-import") (part "R-EU_0207/10"))
    )
    (comp (ref "RX-2")
      (value "R-EU_0207/10")
      (footprint "eagle-import:0207_10")
      (libsource (lib "eagle-import") (part "R-EU_0207/10"))
    )
    (comp (ref "RX-3")
      (value "R-EU_0207/10")
      (footprint "eagle-import:0207_10")
      (libsource (lib "eagle-import") (part "R-EU_0207/10"))
    )
    (comp (ref "RX-4")
      (value "R-EU_0207/10")
      (footprint "eagle-import:0207_10")
      (libsource (lib "eagle-import") (part "R-EU_0207/10"))
    )
    (comp (ref "RX-5")
      (value "R-EU_0207/10")
      (footprint "eagle-import:0207_10")
      (libsource (lib "eagle-import") (part "R-EU_0207/10"))
    )
    (comp (ref "RX-6")
      (value "R-EU_0207/10")
      (footprint "eagle-import:0207_10")
      (libsource (lib "eagle-import") (part "R-EU_0207/10"))
    )
    (comp (ref "RX-7")
      (value "R-EU_0207/10")
      (footprint "eagle-import:0207_10")
      (libsource (lib "eagle-import") (part "R-EU_0207/10"))
    )
    (comp (ref "RX-8")
      (value "R-EU_0207/10")
      (footprint "eagle-import:0207_10")
      (libsource (lib "eagle-import") (part "R-EU_0207/10"))
    )
    (comp (ref "RXO-0")
      (value "R-EU_0207/10")
      (footprint "eagle-import:0207_10")
      (libsource (lib "eagle-import") (part "R-EU_0207/10"))
    )
    (comp (ref "RXO-1")
      (value "R-EU_0207/10")
      (footprint "eagle-import:0207_10")
      (libsource (lib "eagle-import") (part "R-EU_0207/10"))
    )
    (comp (ref "RXO-2")
      (value "R-EU_0207/10")
      (footprint "eagle-import:0207_10")
      (libsource (lib "eagle-import") (part "R-EU_0207/10"))
    )
    (comp (ref "RXO-3")
      (value "R-EU_0207/10")
      (footprint "eagle-import:0207_10")
      (libsource (lib "eagle-import") (part "R-EU_0207/10"))
    )
    (comp (ref "RXO-4")
      (value "R-EU_0207/10")
      (footprint "eagle-import:0207_10")
      (libsource (lib "eagle-import") (part "R-EU_0207/10"))
    )
    (comp (ref "RXO-5")
      (value "R-EU_0207/10")
      (footprint "eagle-import:0207_10")
      (libsource (lib "eagle-import") (part "R-EU_0207/10"))
    )
    (comp (ref "RXO-6")
      (value "R-EU_0207/10")
      (footprint "eagle-import:0207_10")
      (libsource (lib "eagle-import") (part "R-EU_0207/10"))
    )
    (comp (ref "RXO-7")
      (value "R-EU_0207/10")
      (footprint "eagle-import:0207_10")
      (libsource (lib "eagle-import") (part "R-EU_0207/10"))
    )
    (comp (ref "RY-0")
      (value "R-EU_0207/10")
      (footprint "eagle-import:0207_10")
      (libsource (lib "eagle-import") (part "R-EU_0207/10"))
    )
    (comp (ref "RY-1")
      (value "R-EU_0207/10")
      (footprint "eagle-import:0207_10")
      (libsource (lib "eagle-import") (part "R-EU_0207/10"))
    )
    (comp (ref "RY-2")
      (value "R-EU_0207/10")
      (footprint "eagle-import:0207_10")
      (libsource (lib "eagle-import") (part "R-EU_0207/10"))
    )
    (comp (ref "RY-3")
      (value "R-EU_0207/10")
      (footprint "eagle-import:0207_10")
      (libsource (lib "eagle-import") (part "R-EU_0207/10"))
    )
    (comp (ref "RY-4")
      (value "R-EU_0207/10")
      (footprint "eagle-import:0207_10")
      (libsource (lib "eagle-import") (part "R-EU_0207/10"))
    )
    (comp (ref "RY-5")
      (value "R-EU_0207/10")
      (footprint "eagle-import:0207_10")
      (libsource (lib "eagle-import") (part "R-EU_0207/10"))
    )
    (comp (ref "RY-6")
      (value "R-EU_0207/10")
      (footprint "eagle-import:0207_10")
      (libsource (lib "eagle-import") (part "R-EU_0207/10"))
    )
    (comp (ref "RY-7")
      (value "R-EU_0207/10")
      (footprint "eagle-import:0207_10")
      (libsource (lib "eagle-import") (part "R-EU_0207/10"))
    )
    (comp (ref "TH")
      (value "7486N")
      (footprint "eagle-import:DIL14")
      (libsource (lib "eagle-import") (part "7486N"))
    )
    (comp (ref "TL")
      (value "7486N")
      (footprint "eagle-import:DIL14")
      (libsource (lib "eagle-import") (part "7486N"))
    )
    (comp (ref "X")
      (value "74273N")
      (footprint "eagle-import:DIL20")
      (libsource (lib "eagle-import") (part "74273N"))
    )
    (comp (ref "XB")
      (value "74245N")
      (footprint "eagle-import:DIL20")
      (libsource (lib "eagle-import") (part "74245N"))
    )
    (comp (ref "XOB")
      (value "74245N")
      (footprint "eagle-import:DIL20")
      (libsource (lib "eagle-import") (part "74245N"))
    )
    (comp (ref "XOH")
      (value "7486N")
      (footprint "eagle-import:DIL14")
      (libsource (lib "eagle-import") (part "7486N"))
    )
    (comp (ref "XOL")
      (value "7486N")
      (footprint "eagle-import:DIL14")
      (libsource (lib "eagle-import") (part "7486N"))
    )
    (comp (ref "Y")
      (value "74273N")
      (footprint "eagle-import:DIL20")
      (libsource (lib "eagle-import") (part "74273N"))
    )
    (comp (ref "YB")
      (value "74245N")
      (footprint "eagle-import:DIL20")
      (libsource (lib "eagle-import") (part "74245N"))
    )
    (comp (ref "ZH")
      (value "7408N")
      (footprint "eagle-import:DIL14")
      (libsource (lib "eagle-import") (part "7408N"))
    )
    (comp (ref "ZL")
      (value "7402N")
      (footprint "eagle-import:DIL14")
      (libsource (lib "eagle-import") (part "7402N"))
    )
  )
  (nets
    (net (code "1") (name "A-B") (class "Default")
      (node (ref "AB") (pin "19") (pinfunction "~{G}_19") (pintype "input"))
    )
    (net (code "2") (name "A-C") (class "Default")
      (node (ref "A") (pin "11") (pinfunction "CLK_11") (pintype "input"))
    )
    (net (code "3") (name "A0") (class "Default")
      (node (ref "A") (pin "2") (pinfunction "1Q_2") (pintype "output"))
      (node (ref "AB") (pin "2") (pinfunction "A1_2") (pintype "bidirectional"))
      (node (ref "AL") (pin "5") (pinfunction "A1_5") (pintype "input"))
      (node (ref "ANL") (pin "1") (pinfunction "A_1") (pintype "input"))
      (node (ref "ORL") (pin "1") (pinfunction "A_1") (pintype "input"))
      (node (ref "RA-0") (pin "2") (pinfunction "2_2") (pintype "passive"))
      (node (ref "XOL") (pin "1") (pinfunction "A_1") (pintype "input"))
    )
    (net (code "4") (name "A1") (class "Default")
      (node (ref "A") (pin "5") (pinfunction "2Q_5") (pintype "output"))
      (node (ref "AB") (pin "3") (pinfunction "A2_3") (pintype "bidirectional"))
      (node (ref "AL") (pin "3") (pinfunction "A2_3") (pintype "input"))
      (node (ref "ANL") (pin "4") (pinfunction "A_4") (pintype "input"))
      (node (ref "ORL") (pin "4") (pinfunction "A_4") (pintype "input"))
      (node (ref "RA-1") (pin "2") (pinfunction "2_2") (pintype "passive"))
      (node (ref "XOL") (pin "4") (pinfunction "A_4") (pintype "input"))
    )
    (net (code "5") (name "A2") (class "Default")
      (node (ref "A") (pin "6") (pinfunction "3Q_6") (pintype "output"))
      (node (ref "AB") (pin "4") (pinfunction "A3_4") (pintype "bidirectional"))
      (node (ref "AL") (pin "14") (pinfunction "A3_14") (pintype "input"))
      (node (ref "ANL") (pin "9") (pinfunction "A_9") (pintype "input"))
      (node (ref "ORL") (pin "9") (pinfunction "A_9") (pintype "input"))
      (node (ref "RA-2") (pin "2") (pinfunction "2_2") (pintype "passive"))
      (node (ref "XOL") (pin "9") (pinfunction "A_9") (pintype "input"))
    )
    (net (code "6") (name "A3") (class "Default")
      (node (ref "A") (pin "9") (pinfunction "4Q_9") (pintype "output"))
      (node (ref "AB") (pin "5") (pinfunction "A4_5") (pintype "bidirectional"))
      (node (ref "AL") (pin "12") (pinfunction "A4_12") (pintype "input"))
      (node (ref "ANL") (pin "12") (pinfunction "A_12") (pintype "input"))
      (node (ref "ORL") (pin "12") (pinfunction "A_12") (pintype "input"))
      (node (ref "RA-3") (pin "2") (pinfunction "2_2") (pintype "passive"))
      (node (ref "XOL") (pin "12") (pinfunction "A_12") (pintype "input"))
    )
    (net (code "7") (name "A4") (class "Default")
      (node (ref "A") (pin "12") (pinfunction "5Q_12") (pintype "output"))
      (node (ref "AB") (pin "6") (pinfunction "A5_6") (pintype "bidirectional"))
      (node (ref "AH") (pin "5") (pinfunction "A1_5") (pintype "input"))
      (node (ref "ANH") (pin "1") (pinfunction "A_1") (pintype "input"))
      (node (ref "ORH") (pin "1") (pinfunction "A_1") (pintype "input"))
      (node (ref "RA-4") (pin "2") (pinfunction "2_2") (pintype "passive"))
      (node (ref "XOH") (pin "1") (pinfunction "A_1") (pintype "input"))
    )
    (net (code "8") (name "A5") (class "Default")
      (node (ref "A") (pin "15") (pinfunction "6Q_15") (pintype "output"))
      (node (ref "AB") (pin "7") (pinfunction "A6_7") (pintype "bidirectional"))
      (node (ref "AH") (pin "3") (pinfunction "A2_3") (pintype "input"))
      (node (ref "ANH") (pin "4") (pinfunction "A_4") (pintype "input"))
      (node (ref "ORH") (pin "4") (pinfunction "A_4") (pintype "input"))
      (node (ref "RA-5") (pin "2") (pinfunction "2_2") (pintype "passive"))
      (node (ref "XOH") (pin "4") (pinfunction "A_4") (pintype "input"))
    )
    (net (code "9") (name "A6") (class "Default")
      (node (ref "A") (pin "16") (pinfunction "7Q_16") (pintype "output"))
      (node (ref "AB") (pin "8") (pinfunction "A7_8") (pintype "bidirectional"))
      (node (ref "AH") (pin "14") (pinfunction "A3_14") (pintype "input"))
      (node (ref "ANH") (pin "9") (pinfunction "A_9") (pintype "input"))
      (node (ref "ORH") (pin "9") (pinfunction "A_9") (pintype "input"))
      (node (ref "RA-6") (pin "2") (pinfunction "2_2") (pintype "passive"))
      (node (ref "XOH") (pin "9") (pinfunction "A_9") (pintype "input"))
    )
    (net (code "10") (name "A7") (class "Default")
      (node (ref "A") (pin "19") (pinfunction "8Q_19") (pintype "output"))
      (node (ref "AB") (pin "9") (pinfunction "A8_9") (pintype "bidirectional"))
      (node (ref "AH") (pin "12") (pinfunction "A4_12") (pintype "input"))
      (node (ref "ANH") (pin "12") (pinfunction "A_12") (pintype "input"))
      (node (ref "ORH") (pin "12") (pinfunction "A_12") (pintype "input"))
      (node (ref "RA-7") (pin "2") (pinfunction "2_2") (pintype "passive"))
      (node (ref "XOH") (pin "12") (pinfunction "A_12") (pintype "input"))
    )
    (net (code "11") (name "AD0") (class "Default")
      (node (ref "AL") (pin "4") (pinfunction "S1_4") (pintype "output"))
      (node (ref "ASB") (pin "2") (pinfunction "A1_2") (pintype "bidirectional"))
      (node (ref "RAD-0") (pin "2") (pinfunction "2_2") (pintype "passive"))
      (node (ref "ZL") (pin "2") (pinfunction "A_2") (pintype "input"))
    )
    (net (code "12") (name "AD1") (class "Default")
      (node (ref "AL") (pin "1") (pinfunction "S2_1") (pintype "output"))
      (node (ref "ASB") (pin "3") (pinfunction "A2_3") (pintype "bidirectional"))
      (node (ref "RAD-1") (pin "2") (pinfunction "2_2") (pintype "passive"))
      (node (ref "ZL") (pin "3") (pinfunction "B_3") (pintype "input"))
    )
    (net (code "13") (name "AD2") (class "Default")
      (node (ref "AL") (pin "13") (pinfunction "S3_13") (pintype "output"))
      (node (ref "ASB") (pin "4") (pinfunction "A3_4") (pintype "bidirectional"))
      (node (ref "RAD-2") (pin "2") (pinfunction "2_2") (pintype "passive"))
      (node (ref "ZL") (pin "5") (pinfunction "A_5") (pintype "input"))
    )
    (net (code "14") (name "AD3") (class "Default")
      (node (ref "AL") (pin "10") (pinfunction "S4_10") (pintype "output"))
      (node (ref "ASB") (pin "5") (pinfunction "A4_5") (pintype "bidirectional"))
      (node (ref "RAD-3") (pin "2") (pinfunction "2_2") (pintype "passive"))
      (node (ref "ZL") (pin "6") (pinfunction "B_6") (pintype "input"))
    )
    (net (code "15") (name "AD4") (class "Default")
      (node (ref "AH") (pin "4") (pinfunction "S1_4") (pintype "output"))
      (node (ref "ASB") (pin "6") (pinfunction "A5_6") (pintype "bidirectional"))
      (node (ref "RAD-4") (pin "2") (pinfunction "2_2") (pintype "passive"))
      (node (ref "ZL") (pin "8") (pinfunction "A_8") (pintype "input"))
    )
    (net (code "16") (name "AD5") (class "Default")
      (node (ref "AH") (pin "1") (pinfunction "S2_1") (pintype "output"))
      (node (ref "ASB") (pin "7") (pinfunction "A6_7") (pintype "bidirectional"))
      (node (ref "RAD-5") (pin "2") (pinfunction "2_2") (pintype "passive"))
      (node (ref "ZL") (pin "9") (pinfunction "B_9") (pintype "input"))
    )
    (net (code "17") (name "AD6") (class "Default")
      (node (ref "AH") (pin "13") (pinfunction "S3_13") (pintype "output"))
      (node (ref "ASB") (pin "8") (pinfunction "A7_8") (pintype "bidirectional"))
      (node (ref "RAD-6") (pin "2") (pinfunction "2_2") (pintype "passive"))
      (node (ref "ZL") (pin "11") (pinfunction "A_11") (pintype "input"))
    )
    (net (code "18") (name "AD7") (class "Default")
      (node (ref "AH") (pin "10") (pinfunction "S4_10") (pintype "output"))
      (node (ref "ASB") (pin "9") (pinfunction "A8_9") (pintype "bidirectional"))
      (node (ref "RAD-7") (pin "2") (pinfunction "2_2") (pintype "passive"))
      (node (ref "ZL") (pin "12") (pinfunction "B_12") (pintype "input"))
    )
    (net (code "19") (name "ADD-B") (class "Default")
      (node (ref "ASB") (pin "19") (pinfunction "~{G}_19") (pintype "input"))
    )
    (net (code "20") (name "ADD-SUB") (class "Default")
      (node (ref "AL") (pin "7") (pinfunction "C0_7") (pintype "input"))
      (node (ref "TH") (pin "1") (pinfunction "A_1") (pintype "input"))
      (node (ref "TH") (pin "12") (pinfunction "A_12") (pintype "input"))
      (node (ref "TH") (pin "4") (pinfunction "A_4") (pintype "input"))
      (node (ref "TH") (pin "9") (pinfunction "A_9") (pintype "input"))
      (node (ref "TL") (pin "1") (pinfunction "A_1") (pintype "input"))
      (node (ref "TL") (pin "12") (pinfunction "A_12") (pintype "input"))
      (node (ref "TL") (pin "4") (pinfunction "A_4") (pintype "input"))
      (node (ref "TL") (pin "9") (pinfunction "A_9") (pintype "input"))
    )
    (net (code "21") (name "AN-B") (class "Default")
      (node (ref "ANB") (pin "19") (pinfunction "~{G}_19") (pintype "input"))
    )
    (net (code "22") (name "AN0") (class "Default")
      (node (ref "ANB") (pin "2") (pinfunction "A1_2") (pintype "bidirectional"))
      (node (ref "ANL") (pin "3") (pinfunction "Y_3") (pintype "output"))
      (node (ref "RAN-0") (pin "2") (pinfunction "2_2") (pintype "passive"))
    )
    (net (code "23") (name "AN1") (class "Default")
      (node (ref "ANB") (pin "3") (pinfunction "A2_3") (pintype "bidirectional"))
      (node (ref "ANL") (pin "6") (pinfunction "Y_6") (pintype "output"))
      (node (ref "RAN-1") (pin "2") (pinfunction "2_2") (pintype "passive"))
    )
    (net (code "24") (name "AN2") (class "Default")
      (node (ref "ANB") (pin "4") (pinfunction "A3_4") (pintype "bidirectional"))
      (node (ref "ANL") (pin "8") (pinfunction "Y_8") (pintype "output"))
      (node (ref "RAN-2") (pin "2") (pinfunction "2_2") (pintype "passive"))
    )
    (net (code "25") (name "AN3") (class "Default")
      (node (ref "ANB") (pin "5") (pinfunction "A4_5") (pintype "bidirectional"))
      (node (ref "ANL") (pin "11") (pinfunction "Y_11") (pintype "output"))
      (node (ref "RAN-3") (pin "2") (pinfunction "2_2") (pintype "passive"))
    )
    (net (code "26") (name "AN4") (class "Default")
      (node (ref "ANB") (pin "6") (pinfunction "A5_6") (pintype "bidirectional"))
      (node (ref "ANH") (pin "3") (pinfunction "Y_3") (pintype "output"))
      (node (ref "RAN-4") (pin "2") (pinfunction "2_2") (pintype "passive"))
    )
    (net (code "27") (name "AN5") (class "Default")
      (node (ref "ANB") (pin "7") (pinfunction "A6_7") (pintype "bidirectional"))
      (node (ref "ANH") (pin "6") (pinfunction "Y_6") (pintype "output"))
      (node (ref "RAN-5") (pin "2") (pinfunction "2_2") (pintype "passive"))
    )
    (net (code "28") (name "AN6") (class "Default")
      (node (ref "ANB") (pin "8") (pinfunction "A7_8") (pintype "bidirectional"))
      (node (ref "ANH") (pin "8") (pinfunction "Y_8") (pintype "output"))
      (node (ref "RAN-6") (pin "2") (pinfunction "2_2") (pintype "passive"))
    )
    (net (code "29") (name "AN7") (class "Default")
      (node (ref "ANB") (pin "9") (pinfunction "A8_9") (pintype "bidirectional"))
      (node (ref "ANH") (pin "11") (pinfunction "Y_11") (pintype "output"))
      (node (ref "RAN-7") (pin "2") (pinfunction "2_2") (pintype "passive"))
    )
    (net (code "30") (name "B0") (class "Default")
      (node (ref "A") (pin "3") (pinfunction "1D_3") (pintype "input"))
      (node (ref "AB") (pin "18") (pinfunction "B1_18") (pintype "bidirectional"))
      (node (ref "ANB") (pin "18") (pinfunction "B1_18") (pintype "bidirectional"))
      (node (ref "ANL") (pin "2") (pinfunction "B_2") (pintype "input"))
      (node (ref "ASB") (pin "18") (pinfunction "B1_18") (pintype "bidirectional"))
      (node (ref "NOB") (pin "18") (pinfunction "B1_18") (pintype "bidirectional"))
      (node (ref "NOL") (pin "1") (pinfunction "A_1") (pintype "input"))
      (node (ref "ORB") (pin "18") (pinfunction "B1_18") (pintype "bidirectional"))
      (node (ref "ORL") (pin "2") (pinfunction "B_2") (pintype "input"))
      (node (ref "PH-S") (pin "18") (pinfunction "B1_18") (pintype "bidirectional"))
      (node (ref "PL-S") (pin "18") (pinfunction "B1_18") (pintype "bidirectional"))
      (node (ref "PR-H") (pin "3") (pinfunction "1D_3") (pintype "input"))
      (node (ref "PR-L") (pin "3") (pinfunction "1D_3") (pintype "input"))
      (node (ref "ROM-B") (pin "18") (pinfunction "B1_18") (pintype "bidirectional"))
      (node (ref "TL") (pin "2") (pinfunction "B_2") (pintype "input"))
      (node (ref "X") (pin "3") (pinfunction "1D_3") (pintype "input"))
      (node (ref "XB") (pin "18") (pinfunction "B1_18") (pintype "bidirectional"))
      (node (ref "XOB") (pin "18") (pinfunction "B1_18") (pintype "bidirectional"))
      (node (ref "XOL") (pin "2") (pinfunction "B_2") (pintype "input"))
      (node (ref "Y") (pin "3") (pinfunction "1D_3") (pintype "input"))
      (node (ref "YB") (pin "18") (pinfunction "B1_18") (pintype "bidirectional"))
    )
    (net (code "31") (name "B1") (class "Default")
      (node (ref "A") (pin "4") (pinfunction "2D_4") (pintype "input"))
      (node (ref "AB") (pin "17") (pinfunction "B2_17") (pintype "bidirectional"))
      (node (ref "ANB") (pin "17") (pinfunction "B2_17") (pintype "bidirectional"))
      (node (ref "ANL") (pin "5") (pinfunction "B_5") (pintype "input"))
      (node (ref "ASB") (pin "17") (pinfunction "B2_17") (pintype "bidirectional"))
      (node (ref "NOB") (pin "17") (pinfunction "B2_17") (pintype "bidirectional"))
      (node (ref "NOL") (pin "3") (pinfunction "A_3") (pintype "input"))
      (node (ref "ORB") (pin "17") (pinfunction "B2_17") (pintype "bidirectional"))
      (node (ref "ORL") (pin "5") (pinfunction "B_5") (pintype "input"))
      (node (ref "PH-S") (pin "17") (pinfunction "B2_17") (pintype "bidirectional"))
      (node (ref "PL-S") (pin "17") (pinfunction "B2_17") (pintype "bidirectional"))
      (node (ref "PR-H") (pin "4") (pinfunction "2D_4") (pintype "input"))
      (node (ref "PR-L") (pin "4") (pinfunction "2D_4") (pintype "input"))
      (node (ref "ROM-B") (pin "17") (pinfunction "B2_17") (pintype "bidirectional"))
      (node (ref "TL") (pin "5") (pinfunction "B_5") (pintype "input"))
      (node (ref "X") (pin "4") (pinfunction "2D_4") (pintype "input"))
      (node (ref "XB") (pin "17") (pinfunction "B2_17") (pintype "bidirectional"))
      (node (ref "XOB") (pin "17") (pinfunction "B2_17") (pintype "bidirectional"))
      (node (ref "XOL") (pin "5") (pinfunction "B_5") (pintype "input"))
      (node (ref "Y") (pin "4") (pinfunction "2D_4") (pintype "input"))
      (node (ref "YB") (pin "17") (pinfunction "B2_17") (pintype "bidirectional"))
    )
    (net (code "32") (name "B2") (class "Default")
      (node (ref "A") (pin "7") (pinfunction "3D_7") (pintype "input"))
      (node (ref "AB") (pin "16") (pinfunction "B3_16") (pintype "bidirectional"))
      (node (ref "ANB") (pin "16") (pinfunction "B3_16") (pintype "bidirectional"))
      (node (ref "ANL") (pin "10") (pinfunction "B_10") (pintype "input"))
      (node (ref "ASB") (pin "16") (pinfunction "B3_16") (pintype "bidirectional"))
      (node (ref "NOB") (pin "16") (pinfunction "B3_16") (pintype "bidirectional"))
      (node (ref "NOL") (pin "5") (pinfunction "A_5") (pintype "input"))
      (node (ref "ORB") (pin "16") (pinfunction "B3_16") (pintype "bidirectional"))
      (node (ref "ORL") (pin "10") (pinfunction "B_10") (pintype "input"))
      (node (ref "PH-S") (pin "16") (pinfunction "B3_16") (pintype "bidirectional"))
      (node (ref "PL-S") (pin "16") (pinfunction "B3_16") (pintype "bidirectional"))
      (node (ref "PR-H") (pin "7") (pinfunction "3D_7") (pintype "input"))
      (node (ref "PR-L") (pin "7") (pinfunction "3D_7") (pintype "input"))
      (node (ref "ROM-B") (pin "16") (pinfunction "B3_16") (pintype "bidirectional"))
      (node (ref "TL") (pin "10") (pinfunction "B_10") (pintype "input"))
      (node (ref "X") (pin "7") (pinfunction "3D_7") (pintype "input"))
      (node (ref "XB") (pin "16") (pinfunction "B3_16") (pintype "bidirectional"))
      (node (ref "XOB") (pin "16") (pinfunction "B3_16") (pintype "bidirectional"))
      (node (ref "XOL") (pin "10") (pinfunction "B_10") (pintype "input"))
      (node (ref "Y") (pin "7") (pinfunction "3D_7") (pintype "input"))
      (node (ref "YB") (pin "16") (pinfunction "B3_16") (pintype "bidirectional"))
    )
    (net (code "33") (name "B3") (class "Default")
      (node (ref "A") (pin "8") (pinfunction "4D_8") (pintype "input"))
      (node (ref "AB") (pin "15") (pinfunction "B4_15") (pintype "bidirectional"))
      (node (ref "ANB") (pin "15") (pinfunction "B4_15") (pintype "bidirectional"))
      (node (ref "ANL") (pin "13") (pinfunction "B_13") (pintype "input"))
      (node (ref "ASB") (pin "15") (pinfunction "B4_15") (pintype "bidirectional"))
      (node (ref "NOB") (pin "15") (pinfunction "B4_15") (pintype "bidirectional"))
      (node (ref "NOL") (pin "9") (pinfunction "A_9") (pintype "input"))
      (node (ref "ORB") (pin "15") (pinfunction "B4_15") (pintype "bidirectional"))
      (node (ref "ORL") (pin "13") (pinfunction "B_13") (pintype "input"))
      (node (ref "PH-S") (pin "15") (pinfunction "B4_15") (pintype "bidirectional"))
      (node (ref "PL-S") (pin "15") (pinfunction "B4_15") (pintype "bidirectional"))
      (node (ref "PR-H") (pin "8") (pinfunction "4D_8") (pintype "input"))
      (node (ref "PR-L") (pin "8") (pinfunction "4D_8") (pintype "input"))
      (node (ref "ROM-B") (pin "15") (pinfunction "B4_15") (pintype "bidirectional"))
      (node (ref "TL") (pin "13") (pinfunction "B_13") (pintype "input"))
      (node (ref "X") (pin "8") (pinfunction "4D_8") (pintype "input"))
      (node (ref "XB") (pin "15") (pinfunction "B4_15") (pintype "bidirectional"))
      (node (ref "XOB") (pin "15") (pinfunction "B4_15") (pintype "bidirectional"))
      (node (ref "XOL") (pin "13") (pinfunction "B_13") (pintype "input"))
      (node (ref "Y") (pin "8") (pinfunction "4D_8") (pintype "input"))
      (node (ref "YB") (pin "15") (pinfunction "B4_15") (pintype "bidirectional"))
    )
    (net (code "34") (name "B4") (class "Default")
      (node (ref "A") (pin "13") (pinfunction "5D_13") (pintype "input"))
      (node (ref "AB") (pin "14") (pinfunction "B5_14") (pintype "bidirectional"))
      (node (ref "ANB") (pin "14") (pinfunction "B5_14") (pintype "bidirectional"))
      (node (ref "ANH") (pin "2") (pinfunction "B_2") (pintype "input"))
      (node (ref "ASB") (pin "14") (pinfunction "B5_14") (pintype "bidirectional"))
      (node (ref "NOB") (pin "14") (pinfunction "B5_14") (pintype "bidirectional"))
      (node (ref "NOL") (pin "11") (pinfunction "A_11") (pintype "input"))
      (node (ref "ORB") (pin "14") (pinfunction "B5_14") (pintype "bidirectional"))
      (node (ref "ORH") (pin "2") (pinfunction "B_2") (pintype "input"))
      (node (ref "PH-S") (pin "14") (pinfunction "B5_14") (pintype "bidirectional"))
      (node (ref "PL-S") (pin "14") (pinfunction "B5_14") (pintype "bidirectional"))
      (node (ref "PR-H") (pin "13") (pinfunction "5D_13") (pintype "input"))
      (node (ref "PR-L") (pin "13") (pinfunction "5D_13") (pintype "input"))
      (node (ref "ROM-B") (pin "14") (pinfunction "B5_14") (pintype "bidirectional"))
      (node (ref "TH") (pin "2") (pinfunction "B_2") (pintype "input"))
      (node (ref "X") (pin "13") (pinfunction "5D_13") (pintype "input"))
      (node (ref "XB") (pin "14") (pinfunction "B5_14") (pintype "bidirectional"))
      (node (ref "XOB") (pin "14") (pinfunction "B5_14") (pintype "bidirectional"))
      (node (ref "XOH") (pin "2") (pinfunction "B_2") (pintype "input"))
      (node (ref "Y") (pin "13") (pinfunction "5D_13") (pintype "input"))
      (node (ref "YB") (pin "14") (pinfunction "B5_14") (pintype "bidirectional"))
    )
    (net (code "35") (name "B5") (class "Default")
      (node (ref "A") (pin "14") (pinfunction "6D_14") (pintype "input"))
      (node (ref "AB") (pin "13") (pinfunction "B6_13") (pintype "bidirectional"))
      (node (ref "ANB") (pin "13") (pinfunction "B6_13") (pintype "bidirectional"))
      (node (ref "ANH") (pin "5") (pinfunction "B_5") (pintype "input"))
      (node (ref "ASB") (pin "13") (pinfunction "B6_13") (pintype "bidirectional"))
      (node (ref "NOB") (pin "13") (pinfunction "B6_13") (pintype "bidirectional"))
      (node (ref "NOL") (pin "13") (pinfunction "A_13") (pintype "input"))
      (node (ref "ORB") (pin "13") (pinfunction "B6_13") (pintype "bidirectional"))
      (node (ref "ORH") (pin "5") (pinfunction "B_5") (pintype "input"))
      (node (ref "PL-S") (pin "13") (pinfunction "B6_13") (pintype "bidirectional"))
      (node (ref "PR-L") (pin "14") (pinfunction "6D_14") (pintype "input"))
      (node (ref "ROM-B") (pin "13") (pinfunction "B6_13") (pintype "bidirectional"))
      (node (ref "TH") (pin "5") (pinfunction "B_5") (pintype "input"))
      (node (ref "X") (pin "14") (pinfunction "6D_14") (pintype "input"))
      (node (ref "XB") (pin "13") (pinfunction "B6_13") (pintype "bidirectional"))
      (node (ref "XOB") (pin "13") (pinfunction "B6_13") (pintype "bidirectional"))
      (node (ref "XOH") (pin "5") (pinfunction "B_5") (pintype "input"))
      (node (ref "Y") (pin "14") (pinfunction "6D_14") (pintype "input"))
      (node (ref "YB") (pin "13") (pinfunction "B6_13") (pintype "bidirectional"))
    )
    (net (code "36") (name "B6") (class "Default")
      (node (ref "A") (pin "17") (pinfunction "7D_17") (pintype "input"))
      (node (ref "AB") (pin "12") (pinfunction "B7_12") (pintype "bidirectional"))
      (node (ref "ANB") (pin "12") (pinfunction "B7_12") (pintype "bidirectional"))
      (node (ref "ANH") (pin "10") (pinfunction "B_10") (pintype "input"))
      (node (ref "ASB") (pin "12") (pinfunction "B7_12") (pintype "bidirectional"))
      (node (ref "NOB") (pin "12") (pinfunction "B7_12") (pintype "bidirectional"))
      (node (ref "NOH") (pin "1") (pinfunction "A_1") (pintype "input"))
      (node (ref "ORB") (pin "12") (pinfunction "B7_12") (pintype "bidirectional"))
      (node (ref "ORH") (pin "10") (pinfunction "B_10") (pintype "input"))
      (node (ref "PL-S") (pin "12") (pinfunction "B7_12") (pintype "bidirectional"))
      (node (ref "PR-L") (pin "17") (pinfunction "7D_17") (pintype "input"))
      (node (ref "ROM-B") (pin "12") (pinfunction "B7_12") (pintype "bidirectional"))
      (node (ref "TH") (pin "10") (pinfunction "B_10") (pintype "input"))
      (node (ref "X") (pin "17") (pinfunction "7D_17") (pintype "input"))
      (node (ref "XB") (pin "12") (pinfunction "B7_12") (pintype "bidirectional"))
      (node (ref "XOB") (pin "12") (pinfunction "B7_12") (pintype "bidirectional"))
      (node (ref "XOH") (pin "10") (pinfunction "B_10") (pintype "input"))
      (node (ref "Y") (pin "17") (pinfunction "7D_17") (pintype "input"))
      (node (ref "YB") (pin "12") (pinfunction "B7_12") (pintype "bidirectional"))
    )
    (net (code "37") (name "B7") (class "Default")
      (node (ref "A") (pin "18") (pinfunction "8D_18") (pintype "input"))
      (node (ref "AB") (pin "11") (pinfunction "B8_11") (pintype "bidirectional"))
      (node (ref "ANB") (pin "11") (pinfunction "B8_11") (pintype "bidirectional"))
      (node (ref "ANH") (pin "13") (pinfunction "B_13") (pintype "input"))
      (node (ref "ASB") (pin "11") (pinfunction "B8_11") (pintype "bidirectional"))
      (node (ref "NOB") (pin "11") (pinfunction "B8_11") (pintype "bidirectional"))
      (node (ref "NOH") (pin "3") (pinfunction "A_3") (pintype "input"))
      (node (ref "ORB") (pin "11") (pinfunction "B8_11") (pintype "bidirectional"))
      (node (ref "ORH") (pin "13") (pinfunction "B_13") (pintype "input"))
      (node (ref "PL-S") (pin "11") (pinfunction "B8_11") (pintype "bidirectional"))
      (node (ref "PR-L") (pin "18") (pinfunction "8D_18") (pintype "input"))
      (node (ref "ROM-B") (pin "11") (pinfunction "B8_11") (pintype "bidirectional"))
      (node (ref "TH") (pin "13") (pinfunction "B_13") (pintype "input"))
      (node (ref "X") (pin "18") (pinfunction "8D_18") (pintype "input"))
      (node (ref "XB") (pin "11") (pinfunction "B8_11") (pintype "bidirectional"))
      (node (ref "XOB") (pin "11") (pinfunction "B8_11") (pintype "bidirectional"))
      (node (ref "XOH") (pin "13") (pinfunction "B_13") (pintype "input"))
      (node (ref "Y") (pin "18") (pinfunction "8D_18") (pintype "input"))
      (node (ref "YB") (pin "11") (pinfunction "B8_11") (pintype "bidirectional"))
    )
    (net (code "38") (name "CO") (class "Default")
      (node (ref "AH") (pin "7") (pinfunction "C0_7") (pintype "input"))
      (node (ref "AL") (pin "9") (pinfunction "C4_9") (pintype "output"))
      (node (ref "RC") (pin "2") (pinfunction "2_2") (pintype "passive"))
    )
    (net (code "39") (name "GND") (class "Default")
      (node (ref "A") (pin "10") (pinfunction "-UB_10") (pintype "power_in"))
      (node (ref "AB") (pin "10") (pinfunction "-UB_10") (pintype "power_in"))
      (node (ref "AH") (pin "8") (pinfunction "-UB_8") (pintype "power_in"))
      (node (ref "AL") (pin "8") (pinfunction "-UB_8") (pintype "power_in"))
      (node (ref "ANB") (pin "10") (pinfunction "-UB_10") (pintype "power_in"))
      (node (ref "ANH") (pin "7") (pinfunction "-UB_7") (pintype "power_in"))
      (node (ref "ANL") (pin "7") (pinfunction "-UB_7") (pintype "power_in"))
      (node (ref "ASB") (pin "10") (pinfunction "-UB_10") (pintype "power_in"))
      (node (ref "LA-0") (pin "K") (pinfunction "C_K") (pintype "passive"))
      (node (ref "LA-1") (pin "K") (pinfunction "C_K") (pintype "passive"))
      (node (ref "LA-2") (pin "K") (pinfunction "C_K") (pintype "passive"))
      (node (ref "LA-3") (pin "K") (pinfunction "C_K") (pintype "passive"))
      (node (ref "LA-4") (pin "K") (pinfunction "C_K") (pintype "passive"))
      (node (ref "LA-5") (pin "K") (pinfunction "C_K") (pintype "passive"))
      (node (ref "LA-6") (pin "K") (pinfunction "C_K") (pintype "passive"))
      (node (ref "LA-7") (pin "K") (pinfunction "C_K") (pintype "passive"))
      (node (ref "LAD-0") (pin "K") (pinfunction "C_K") (pintype "passive"))
      (node (ref "LAD-1") (pin "K") (pinfunction "C_K") (pintype "passive"))
      (node (ref "LAD-2") (pin "K") (pinfunction "C_K") (pintype "passive"))
      (node (ref "LAD-3") (pin "K") (pinfunction "C_K") (pintype "passive"))
      (node (ref "LAD-4") (pin "K") (pinfunction "C_K") (pintype "passive"))
      (node (ref "LAD-5") (pin "K") (pinfunction "C_K") (pintype "passive"))
      (node (ref "LAD-6") (pin "K") (pinfunction "C_K") (pintype "passive"))
      (node (ref "LAD-7") (pin "K") (pinfunction "C_K") (pintype "passive"))
      (node (ref "LAN-0") (pin "K") (pinfunction "C_K") (pintype "passive"))
      (node (ref "LAN-1") (pin "K") (pinfunction "C_K") (pintype "passive"))
      (node (ref "LAN-2") (pin "K") (pinfunction "C_K") (pintype "passive"))
      (node (ref "LAN-3") (pin "K") (pinfunction "C_K") (pintype "passive"))
      (node (ref "LAN-4") (pin "K") (pinfunction "C_K") (pintype "passive"))
      (node (ref "LAN-5") (pin "K") (pinfunction "C_K") (pintype "passive"))
      (node (ref "LAN-6") (pin "K") (pinfunction "C_K") (pintype "passive"))
      (node (ref "LAN-7") (pin "K") (pinfunction "C_K") (pintype "passive"))
      (node (ref "LC") (pin "K") (pinfunction "C_K") (pintype "passive"))
      (node (ref "LNO-0") (pin "K") (pinfunction "C_K") (pintype "passive"))
      (node (ref "LNO-1") (pin "K") (pinfunction "C_K") (pintype "passive"))
      (node (ref "LNO-2") (pin "K") (pinfunction "C_K") (pintype "passive"))
      (node (ref "LNO-3") (pin "K") (pinfunction "C_K") (pintype "passive"))
      (node (ref "LNO-4") (pin "K") (pinfunction "C_K") (pintype "passive"))
      (node (ref "LNO-5") (pin "K") (pinfunction "C_K") (pintype "passive"))
      (node (ref "LNO-6") (pin "K") (pinfunction "C_K") (pintype "passive"))
      (node (ref "LNO-7") (pin "K") (pinfunction "C_K") (pintype "passive"))
      (node (ref "LOF") (pin "K") (pinfunction "C_K") (pintype "passive"))
      (node (ref "LOR-0") (pin "K") (pinfunction "C_K") (pintype "passive"))
      (node (ref "LOR-1") (pin "K") (pinfunction "C_K") (pintype "passive"))
      (node (ref "LOR-2") (pin "K") (pinfunction "C_K") (pintype "passive"))
      (node (ref "LOR-3") (pin "K") (pinfunction "C_K") (pintype "passive"))
      (node (ref "LOR-4") (pin "K") (pinfunction "C_K") (pintype "passive"))
      (node (ref "LOR-5") (pin "K") (pinfunction "C_K") (pintype "passive"))
      (node (ref "LOR-6") (pin "K") (pinfunction "C_K") (pintype "passive"))
      (node (ref "LOR-7") (pin "K") (pinfunction "C_K") (pintype "passive"))
      (node (ref "LPC-0") (pin "K") (pinfunction "C_K") (pintype "passive"))
      (node (ref "LPC-1") (pin "K") (pinfunction "C_K") (pintype "passive"))
      (node (ref "LPC-10") (pin "K") (pinfunction "C_K") (pintype "passive"))
      (node (ref "LPC-11") (pin "K") (pinfunction "C_K") (pintype "passive"))
      (node (ref "LPC-12") (pin "K") (pinfunction "C_K") (pintype "passive"))
      (node (ref "LPC-2") (pin "K") (pinfunction "C_K") (pintype "passive"))
      (node (ref "LPC-3") (pin "K") (pinfunction "C_K") (pintype "passive"))
      (node (ref "LPC-4") (pin "K") (pinfunction "C_K") (pintype "passive"))
      (node (ref "LPC-5") (pin "K") (pinfunction "C_K") (pintype "passive"))
      (node (ref "LPC-6") (pin "K") (pinfunction "C_K") (pintype "passive"))
      (node (ref "LPC-7") (pin "K") (pinfunction "C_K") (pintype "passive"))
      (node (ref "LPC-8") (pin "K") (pinfunction "C_K") (pintype "passive"))
      (node (ref "LPC-9") (pin "K") (pinfunction "C_K") (pintype "passive"))
      (node (ref "LPR-0") (pin "K") (pinfunction "C_K") (pintype "passive"))
      (node (ref "LPR-1") (pin "K") (pinfunction "C_K") (pintype "passive"))
      (node (ref "LPR-10") (pin "K") (pinfunction "C_K") (pintype "passive"))
      (node (ref "LPR-11") (pin "K") (pinfunction "C_K") (pintype "passive"))
      (node (ref "LPR-12") (pin "K") (pinfunction "C_K") (pintype "passive"))
      (node (ref "LPR-2") (pin "K") (pinfunction "C_K") (pintype "passive"))
      (node (ref "LPR-3") (pin "K") (pinfunction "C_K") (pintype "passive"))
      (node (ref "LPR-4") (pin "K") (pinfunction "C_K") (pintype "passive"))
      (node (ref "LPR-5") (pin "K") (pinfunction "C_K") (pintype "passive"))
      (node (ref "LPR-6") (pin "K") (pinfunction "C_K") (pintype "passive"))
      (node (ref "LPR-7") (pin "K") (pinfunction "C_K") (pintype "passive"))
      (node (ref "LPR-8") (pin "K") (pinfunction "C_K") (pintype "passive"))
      (node (ref "LPR-9") (pin "K") (pinfunction "C_K") (pintype "passive"))
      (node (ref "LR-0") (pin "K") (pinfunction "C_K") (pintype "passive"))
      (node (ref "LR-1") (pin "K") (pinfunction "C_K") (pintype "passive"))
      (node (ref "LR-2") (pin "K") (pinfunction "C_K") (pintype "passive"))
      (node (ref "LR-3") (pin "K") (pinfunction "C_K") (pintype "passive"))
      (node (ref "LR-4") (pin "K") (pinfunction "C_K") (pintype "passive"))
      (node (ref "LR-5") (pin "K") (pinfunction "C_K") (pintype "passive"))
      (node (ref "LR-6") (pin "K") (pinfunction "C_K") (pintype "passive"))
      (node (ref "LR-7") (pin "K") (pinfunction "C_K") (pintype "passive"))
      (node (ref "LT-0") (pin "K") (pinfunction "C_K") (pintype "passive"))
      (node (ref "LT-1") (pin "K") (pinfunction "C_K") (pintype "passive"))
      (node (ref "LT-2") (pin "K") (pinfunction "C_K") (pintype "passive"))
      (node (ref "LT-3") (pin "K") (pinfunction "C_K") (pintype "passive"))
      (node (ref "LT-4") (pin "K") (pinfunction "C_K") (pintype "passive"))
      (node (ref "LT-5") (pin "K") (pinfunction "C_K") (pintype "passive"))
      (node (ref "LT-6") (pin "K") (pinfunction "C_K") (pintype "passive"))
      (node (ref "LT-7") (pin "K") (pinfunction "C_K") (pintype "passive"))
      (node (ref "LX-0") (pin "K") (pinfunction "C_K") (pintype "passive"))
      (node (ref "LX-1") (pin "K") (pinfunction "C_K") (pintype "passive"))
      (node (ref "LX-2") (pin "K") (pinfunction "C_K") (pintype "passive"))
      (node (ref "LX-3") (pin "K") (pinfunction "C_K") (pintype "passive"))
      (node (ref "LX-4") (pin "K") (pinfunction "C_K") (pintype "passive"))
      (node (ref "LX-5") (pin "K") (pinfunction "C_K") (pintype "passive"))
      (node (ref "LX-6") (pin "K") (pinfunction "C_K") (pintype "passive"))
      (node (ref "LX-7") (pin "K") (pinfunction "C_K") (pintype "passive"))
      (node (ref "LXO-0") (pin "K") (pinfunction "C_K") (pintype "passive"))
      (node (ref "LXO-1") (pin "K") (pinfunction "C_K") (pintype "passive"))
      (node (ref "LXO-2") (pin "K") (pinfunction "C_K") (pintype "passive"))
      (node (ref "LXO-3") (pin "K") (pinfunction "C_K") (pintype "passive"))
      (node (ref "LXO-4") (pin "K") (pinfunction "C_K") (pintype "passive"))
      (node (ref "LXO-5") (pin "K") (pinfunction "C_K") (pintype "passive"))
      (node (ref "LXO-6") (pin "K") (pinfunction "C_K") (pintype "passive"))
      (node (ref "LXO-7") (pin "K") (pinfunction "C_K") (pintype "passive"))
      (node (ref "LY-0") (pin "K") (pinfunction "C_K") (pintype "passive"))
      (node (ref "LY-1") (pin "K") (pinfunction "C_K") (pintype "passive"))
      (node (ref "LY-2") (pin "K") (pinfunction "C_K") (pintype "passive"))
      (node (ref "LY-3") (pin "K") (pinfunction "C_K") (pintype "passive"))
      (node (ref "LY-4") (pin "K") (pinfunction "C_K") (pintype "passive"))
      (node (ref "LY-5") (pin "K") (pinfunction "C_K") (pintype "passive"))
      (node (ref "LY-6") (pin "K") (pinfunction "C_K") (pintype "passive"))
      (node (ref "LY-7") (pin "K") (pinfunction "C_K") (pintype "passive"))
      (node (ref "NOB") (pin "10") (pinfunction "-UB_10") (pintype "power_in"))
      (node (ref "NOH") (pin "7") (pinfunction "-UB_7") (pintype "power_in"))
      (node (ref "NOL") (pin "7") (pinfunction "-UB_7") (pintype "power_in"))
      (node (ref "ORB") (pin "10") (pinfunction "-UB_10") (pintype "power_in"))
      (node (ref "ORH") (pin "7") (pinfunction "-UB_7") (pintype "power_in"))
      (node (ref "ORL") (pin "7") (pinfunction "-UB_7") (pintype "power_in"))
      (node (ref "PC0") (pin "8") (pinfunction "-UB_8") (pintype "power_in"))
      (node (ref "PC1") (pin "8") (pinfunction "-UB_8") (pintype "power_in"))
      (node (ref "PC2") (pin "8") (pinfunction "-UB_8") (pintype "power_in"))
      (node (ref "PC3") (pin "1") (pinfunction "B_1") (pintype "input"))
      (node (ref "PC3") (pin "10") (pinfunction "C_10") (pintype "input"))
      (node (ref "PC3") (pin "8") (pinfunction "-UB_8") (pintype "power_in"))
      (node (ref "PC3") (pin "9") (pinfunction "D_9") (pintype "input"))
      (node (ref "PH-S") (pin "1") (pinfunction "DIR_1") (pintype "input"))
      (node (ref "PH-S") (pin "10") (pinfunction "-UB_10") (pintype "power_in"))
      (node (ref "PL-S") (pin "1") (pinfunction "DIR_1") (pintype "input"))
      (node (ref "PL-S") (pin "10") (pinfunction "-UB_10") (pintype "power_in"))
      (node (ref "PR-H") (pin "10") (pinfunction "-UB_10") (pintype "power_in"))
      (node (ref "PR-L") (pin "10") (pinfunction "-UB_10") (pintype "power_in"))
      (node (ref "ROM") (pin "14") (pinfunction "GND_14") (pintype "power_in"))
      (node (ref "ROM-B") (pin "10") (pinfunction "-UB_10") (pintype "power_in"))
      (node (ref "TH") (pin "7") (pinfunction "-UB_7") (pintype "power_in"))
      (node (ref "TL") (pin "7") (pinfunction "-UB_7") (pintype "power_in"))
      (node (ref "X") (pin "10") (pinfunction "-UB_10") (pintype "power_in"))
      (node (ref "XB") (pin "10") (pinfunction "-UB_10") (pintype "power_in"))
      (node (ref "XOB") (pin "10") (pinfunction "-UB_10") (pintype "power_in"))
      (node (ref "XOH") (pin "7") (pinfunction "-UB_7") (pintype "power_in"))
      (node (ref "XOL") (pin "7") (pinfunction "-UB_7") (pintype "power_in"))
      (node (ref "Y") (pin "10") (pinfunction "-UB_10") (pintype "power_in"))
      (node (ref "YB") (pin "10") (pinfunction "-UB_10") (pintype "power_in"))
      (node (ref "ZH") (pin "7") (pinfunction "-UB_7") (pintype "power_in"))
      (node (ref "ZL") (pin "7") (pinfunction "-UB_7") (pintype "power_in"))
    )
    (net (code "40") (name "INC") (class "Default")
      (node (ref "PC0") (pin "5") (pinfunction "UP_5") (pintype "input"))
    )
    (net (code "41") (name "LOAD") (class "Default")
      (node (ref "PC0") (pin "11") (pinfunction "~{LOAD}_11") (pintype "input"))
      (node (ref "PC1") (pin "11") (pinfunction "~{LOAD}_11") (pintype "input"))
      (node (ref "PC2") (pin "11") (pinfunction "~{LOAD}_11") (pintype "input"))
      (node (ref "PC3") (pin "11") (pinfunction "~{LOAD}_11") (pintype "input"))
    )
    (net (code "42") (name "N$25") (class "Default")
      (node (ref "RX-8") (pin "2") (pinfunction "2_2") (pintype "passive"))
    )
    (net (code "43") (name "N$103") (class "Default")
      (node (ref "ROM") (pin "20") (pinfunction "~{CE}_20") (pintype "input"))
    )
    (net (code "44") (name "N$104") (class "Default")
      (node (ref "ROM") (pin "27") (pinfunction "~{WE}_27") (pintype "input"))
    )
    (net (code "45") (name "N$105") (class "Default")
      (node (ref "ROM") (pin "22") (pinfunction "~{OE}_22") (pintype "input"))
    )
    (net (code "46") (name "NO-B") (class "Default")
      (node (ref "NOB") (pin "19") (pinfunction "~{G}_19") (pintype "input"))
    )
    (net (code "47") (name "NO0") (class "Default")
      (node (ref "NOB") (pin "2") (pinfunction "A1_2") (pintype "bidirectional"))
      (node (ref "NOL") (pin "2") (pinfunction "Y_2") (pintype "output"))
      (node (ref "RNO-0") (pin "2") (pinfunction "2_2") (pintype "passive"))
    )
    (net (code "48") (name "NO1") (class "Default")
      (node (ref "NOB") (pin "3") (pinfunction "A2_3") (pintype "bidirectional"))
      (node (ref "NOL") (pin "4") (pinfunction "Y_4") (pintype "output"))
      (node (ref "RNO-1") (pin "2") (pinfunction "2_2") (pintype "passive"))
    )
    (net (code "49") (name "NO2") (class "Default")
      (node (ref "NOB") (pin "4") (pinfunction "A3_4") (pintype "bidirectional"))
      (node (ref "NOL") (pin "6") (pinfunction "Y_6") (pintype "output"))
      (node (ref "RNO-2") (pin "2") (pinfunction "2_2") (pintype "passive"))
    )
    (net (code "50") (name "NO3") (class "Default")
      (node (ref "NOB") (pin "5") (pinfunction "A4_5") (pintype "bidirectional"))
      (node (ref "NOL") (pin "8") (pinfunction "Y_8") (pintype "output"))
      (node (ref "RNO-3") (pin "2") (pinfunction "2_2") (pintype "passive"))
    )
    (net (code "51") (name "NO4") (class "Default")
      (node (ref "NOB") (pin "6") (pinfunction "A5_6") (pintype "bidirectional"))
      (node (ref "NOL") (pin "10") (pinfunction "Y_10") (pintype "output"))
      (node (ref "RNO-4") (pin "2") (pinfunction "2_2") (pintype "passive"))
    )
    (net (code "52") (name "NO5") (class "Default")
      (node (ref "NOB") (pin "7") (pinfunction "A6_7") (pintype "bidirectional"))
      (node (ref "NOL") (pin "12") (pinfunction "Y_12") (pintype "output"))
      (node (ref "RNO-5") (pin "2") (pinfunction "2_2") (pintype "passive"))
    )
    (net (code "53") (name "NO6") (class "Default")
      (node (ref "NOB") (pin "8") (pinfunction "A7_8") (pintype "bidirectional"))
      (node (ref "NOH") (pin "2") (pinfunction "Y_2") (pintype "output"))
      (node (ref "RNO-6") (pin "2") (pinfunction "2_2") (pintype "passive"))
    )
    (net (code "54") (name "NO7") (class "Default")
      (node (ref "NOB") (pin "9") (pinfunction "A8_9") (pintype "bidirectional"))
      (node (ref "NOH") (pin "4") (pinfunction "Y_4") (pintype "output"))
      (node (ref "RNO-7") (pin "2") (pinfunction "2_2") (pintype "passive"))
    )
    (net (code "55") (name "Net-(LA-0-PadA)") (class "Default")
      (node (ref "LA-0") (pin "A") (pinfunction "A_A") (pintype "passive"))
      (node (ref "RA-0") (pin "1") (pinfunction "1_1") (pintype "passive"))
    )
    (net (code "56") (name "Net-(LA-1-PadA)") (class "Default")
      (node (ref "LA-1") (pin "A") (pinfunction "A_A") (pintype "passive"))
      (node (ref "RA-1") (pin "1") (pinfunction "1_1") (pintype "passive"))
    )
    (net (code "57") (name "Net-(LA-2-PadA)") (class "Default")
      (node (ref "LA-2") (pin "A") (pinfunction "A_A") (pintype "passive"))
      (node (ref "RA-2") (pin "1") (pinfunction "1_1") (pintype "passive"))
    )
    (net (code "58") (name "Net-(LA-3-PadA)") (class "Default")
      (node (ref "LA-3") (pin "A") (pinfunction "A_A") (pintype "passive"))
      (node (ref "RA-3") (pin "1") (pinfunction "1_1") (pintype "passive"))
    )
    (net (code "59") (name "Net-(LA-4-PadA)") (class "Default")
      (node (ref "LA-4") (pin "A") (pinfunction "A_A") (pintype "passive"))
      (node (ref "RA-4") (pin "1") (pinfunction "1_1") (pintype "passive"))
    )
    (net (code "60") (name "Net-(LA-5-PadA)") (class "Default")
      (node (ref "LA-5") (pin "A") (pinfunction "A_A") (pintype "passive"))
      (node (ref "RA-5") (pin "1") (pinfunction "1_1") (pintype "passive"))
    )
    (net (code "61") (name "Net-(LA-6-PadA)") (class "Default")
      (node (ref "LA-6") (pin "A") (pinfunction "A_A") (pintype "passive"))
      (node (ref "RA-6") (pin "1") (pinfunction "1_1") (pintype "passive"))
    )
    (net (code "62") (name "Net-(LA-7-PadA)") (class "Default")
      (node (ref "LA-7") (pin "A") (pinfunction "A_A") (pintype "passive"))
      (node (ref "RA-7") (pin "1") (pinfunction "1_1") (pintype "passive"))
    )
    (net (code "63") (name "Net-(LAD-0-PadA)") (class "Default")
      (node (ref "LAD-0") (pin "A") (pinfunction "A_A") (pintype "passive"))
      (node (ref "RAD-0") (pin "1") (pinfunction "1_1") (pintype "passive"))
    )
    (net (code "64") (name "Net-(LAD-1-PadA)") (class "Default")
      (node (ref "LAD-1") (pin "A") (pinfunction "A_A") (pintype "passive"))
      (node (ref "RAD-1") (pin "1") (pinfunction "1_1") (pintype "passive"))
    )
    (net (code "65") (name "Net-(LAD-2-PadA)") (class "Default")
      (node (ref "LAD-2") (pin "A") (pinfunction "A_A") (pintype "passive"))
      (node (ref "RAD-2") (pin "1") (pinfunction "1_1") (pintype "passive"))
    )
    (net (code "66") (name "Net-(LAD-3-PadA)") (class "Default")
      (node (ref "LAD-3") (pin "A") (pinfunction "A_A") (pintype "passive"))
      (node (ref "RAD-3") (pin "1") (pinfunction "1_1") (pintype "passive"))
    )
    (net (code "67") (name "Net-(LAD-4-PadA)") (class "Default")
      (node (ref "LAD-4") (pin "A") (pinfunction "A_A") (pintype "passive"))
      (node (ref "RAD-4") (pin "1") (pinfunction "1_1") (pintype "passive"))
    )
    (net (code "68") (name "Net-(LAD-5-PadA)") (class "Default")
      (node (ref "LAD-5") (pin "A") (pinfunction "A_A") (pintype "passive"))
      (node (ref "RAD-5") (pin "1") (pinfunction "1_1") (pintype "passive"))
    )
    (net (code "69") (name "Net-(LAD-6-PadA)") (class "Default")
      (node (ref "LAD-6") (pin "A") (pinfunction "A_A") (pintype "passive"))
      (node (ref "RAD-6") (pin "1") (pinfunction "1_1") (pintype "passive"))
    )
    (net (code "70") (name "Net-(LAD-7-PadA)") (class "Default")
      (node (ref "LAD-7") (pin "A") (pinfunction "A_A") (pintype "passive"))
      (node (ref "RAD-7") (pin "1") (pinfunction "1_1") (pintype "passive"))
    )
    (net (code "71") (name "Net-(LAN-0-PadA)") (class "Default")
      (node (ref "LAN-0") (pin "A") (pinfunction "A_A") (pintype "passive"))
      (node (ref "RAN-0") (pin "1") (pinfunction "1_1") (pintype "passive"))
    )
    (net (code "72") (name "Net-(LAN-1-PadA)") (class "Default")
      (node (ref "LAN-1") (pin "A") (pinfunction "A_A") (pintype "passive"))
      (node (ref "RAN-1") (pin "1") (pinfunction "1_1") (pintype "passive"))
    )
    (net (code "73") (name "Net-(LAN-2-PadA)") (class "Default")
      (node (ref "LAN-2") (pin "A") (pinfunction "A_A") (pintype "passive"))
      (node (ref "RAN-2") (pin "1") (pinfunction "1_1") (pintype "passive"))
    )
    (net (code "74") (name "Net-(LAN-3-PadA)") (class "Default")
      (node (ref "LAN-3") (pin "A") (pinfunction "A_A") (pintype "passive"))
      (node (ref "RAN-3") (pin "1") (pinfunction "1_1") (pintype "passive"))
    )
    (net (code "75") (name "Net-(LAN-4-PadA)") (class "Default")
      (node (ref "LAN-4") (pin "A") (pinfunction "A_A") (pintype "passive"))
      (node (ref "RAN-4") (pin "1") (pinfunction "1_1") (pintype "passive"))
    )
    (net (code "76") (name "Net-(LAN-5-PadA)") (class "Default")
      (node (ref "LAN-5") (pin "A") (pinfunction "A_A") (pintype "passive"))
      (node (ref "RAN-5") (pin "1") (pinfunction "1_1") (pintype "passive"))
    )
    (net (code "77") (name "Net-(LAN-6-PadA)") (class "Default")
      (node (ref "LAN-6") (pin "A") (pinfunction "A_A") (pintype "passive"))
      (node (ref "RAN-6") (pin "1") (pinfunction "1_1") (pintype "passive"))
    )
    (net (code "78") (name "Net-(LAN-7-PadA)") (class "Default")
      (node (ref "LAN-7") (pin "A") (pinfunction "A_A") (pintype "passive"))
      (node (ref "RAN-7") (pin "1") (pinfunction "1_1") (pintype "passive"))
    )
    (net (code "79") (name "Net-(LC-PadA)") (class "Default")
      (node (ref "LC") (pin "A") (pinfunction "A_A") (pintype "passive"))
      (node (ref "RC") (pin "1") (pinfunction "1_1") (pintype "passive"))
    )
    (net (code "80") (name "Net-(LNO-0-PadA)") (class "Default")
      (node (ref "LNO-0") (pin "A") (pinfunction "A_A") (pintype "passive"))
      (node (ref "RNO-0") (pin "1") (pinfunction "1_1") (pintype "passive"))
    )
    (net (code "81") (name "Net-(LNO-1-PadA)") (class "Default")
      (node (ref "LNO-1") (pin "A") (pinfunction "A_A") (pintype "passive"))
      (node (ref "RNO-1") (pin "1") (pinfunction "1_1") (pintype "passive"))
    )
    (net (code "82") (name "Net-(LNO-2-PadA)") (class "Default")
      (node (ref "LNO-2") (pin "A") (pinfunction "A_A") (pintype "passive"))
      (node (ref "RNO-2") (pin "1") (pinfunction "1_1") (pintype "passive"))
    )
    (net (code "83") (name "Net-(LNO-3-PadA)") (class "Default")
      (node (ref "LNO-3") (pin "A") (pinfunction "A_A") (pintype "passive"))
      (node (ref "RNO-3") (pin "1") (pinfunction "1_1") (pintype "passive"))
    )
    (net (code "84") (name "Net-(LNO-4-PadA)") (class "Default")
      (node (ref "LNO-4") (pin "A") (pinfunction "A_A") (pintype "passive"))
      (node (ref "RNO-4") (pin "1") (pinfunction "1_1") (pintype "passive"))
    )
    (net (code "85") (name "Net-(LNO-5-PadA)") (class "Default")
      (node (ref "LNO-5") (pin "A") (pinfunction "A_A") (pintype "passive"))
      (node (ref "RNO-5") (pin "1") (pinfunction "1_1") (pintype "passive"))
    )
    (net (code "86") (name "Net-(LNO-6-PadA)") (class "Default")
      (node (ref "LNO-6") (pin "A") (pinfunction "A_A") (pintype "passive"))
      (node (ref "RNO-6") (pin "1") (pinfunction "1_1") (pintype "passive"))
    )
    (net (code "87") (name "Net-(LNO-7-PadA)") (class "Default")
      (node (ref "LNO-7") (pin "A") (pinfunction "A_A") (pintype "passive"))
      (node (ref "RNO-7") (pin "1") (pinfunction "1_1") (pintype "passive"))
    )
    (net (code "88") (name "Net-(LOF-PadA)") (class "Default")
      (node (ref "LOF") (pin "A") (pinfunction "A_A") (pintype "passive"))
      (node (ref "ROF") (pin "1") (pinfunction "1_1") (pintype "passive"))
    )
    (net (code "89") (name "Net-(LOR-0-PadA)") (class "Default")
      (node (ref "LOR-0") (pin "A") (pinfunction "A_A") (pintype "passive"))
      (node (ref "ROR-0") (pin "1") (pinfunction "1_1") (pintype "passive"))
    )
    (net (code "90") (name "Net-(LOR-1-PadA)") (class "Default")
      (node (ref "LOR-1") (pin "A") (pinfunction "A_A") (pintype "passive"))
      (node (ref "ROR-1") (pin "1") (pinfunction "1_1") (pintype "passive"))
    )
    (net (code "91") (name "Net-(LOR-2-PadA)") (class "Default")
      (node (ref "LOR-2") (pin "A") (pinfunction "A_A") (pintype "passive"))
      (node (ref "ROR-2") (pin "1") (pinfunction "1_1") (pintype "passive"))
    )
    (net (code "92") (name "Net-(LOR-3-PadA)") (class "Default")
      (node (ref "LOR-3") (pin "A") (pinfunction "A_A") (pintype "passive"))
      (node (ref "ROR-3") (pin "1") (pinfunction "1_1") (pintype "passive"))
    )
    (net (code "93") (name "Net-(LOR-4-PadA)") (class "Default")
      (node (ref "LOR-4") (pin "A") (pinfunction "A_A") (pintype "passive"))
      (node (ref "ROR-4") (pin "1") (pinfunction "1_1") (pintype "passive"))
    )
    (net (code "94") (name "Net-(LOR-5-PadA)") (class "Default")
      (node (ref "LOR-5") (pin "A") (pinfunction "A_A") (pintype "passive"))
      (node (ref "ROR-5") (pin "1") (pinfunction "1_1") (pintype "passive"))
    )
    (net (code "95") (name "Net-(LOR-6-PadA)") (class "Default")
      (node (ref "LOR-6") (pin "A") (pinfunction "A_A") (pintype "passive"))
      (node (ref "ROR-6") (pin "1") (pinfunction "1_1") (pintype "passive"))
    )
    (net (code "96") (name "Net-(LOR-7-PadA)") (class "Default")
      (node (ref "LOR-7") (pin "A") (pinfunction "A_A") (pintype "passive"))
      (node (ref "ROR-7") (pin "1") (pinfunction "1_1") (pintype "passive"))
    )
    (net (code "97") (name "Net-(LPC-0-PadA)") (class "Default")
      (node (ref "LPC-0") (pin "A") (pinfunction "A_A") (pintype "passive"))
      (node (ref "RPC-0") (pin "1") (pinfunction "1_1") (pintype "passive"))
    )
    (net (code "98") (name "Net-(LPC-1-PadA)") (class "Default")
      (node (ref "LPC-1") (pin "A") (pinfunction "A_A") (pintype "passive"))
      (node (ref "RPC-1") (pin "1") (pinfunction "1_1") (pintype "passive"))
    )
    (net (code "99") (name "Net-(LPC-2-PadA)") (class "Default")
      (node (ref "LPC-2") (pin "A") (pinfunction "A_A") (pintype "passive"))
      (node (ref "RPC-2") (pin "1") (pinfunction "1_1") (pintype "passive"))
    )
    (net (code "100") (name "Net-(LPC-3-PadA)") (class "Default")
      (node (ref "LPC-3") (pin "A") (pinfunction "A_A") (pintype "passive"))
      (node (ref "RPC-3") (pin "1") (pinfunction "1_1") (pintype "passive"))
    )
    (net (code "101") (name "Net-(LPC-4-PadA)") (class "Default")
      (node (ref "LPC-4") (pin "A") (pinfunction "A_A") (pintype "passive"))
      (node (ref "RPC-4") (pin "1") (pinfunction "1_1") (pintype "passive"))
    )
    (net (code "102") (name "Net-(LPC-5-PadA)") (class "Default")
      (node (ref "LPC-5") (pin "A") (pinfunction "A_A") (pintype "passive"))
      (node (ref "RPC-5") (pin "1") (pinfunction "1_1") (pintype "passive"))
    )
    (net (code "103") (name "Net-(LPC-6-PadA)") (class "Default")
      (node (ref "LPC-6") (pin "A") (pinfunction "A_A") (pintype "passive"))
      (node (ref "RPC-6") (pin "1") (pinfunction "1_1") (pintype "passive"))
    )
    (net (code "104") (name "Net-(LPC-7-PadA)") (class "Default")
      (node (ref "LPC-7") (pin "A") (pinfunction "A_A") (pintype "passive"))
      (node (ref "RPC-7") (pin "1") (pinfunction "1_1") (pintype "passive"))
    )
    (net (code "105") (name "Net-(LPC-8-PadA)") (class "Default")
      (node (ref "LPC-8") (pin "A") (pinfunction "A_A") (pintype "passive"))
      (node (ref "RPC-8") (pin "1") (pinfunction "1_1") (pintype "passive"))
    )
    (net (code "106") (name "Net-(LPC-9-PadA)") (class "Default")
      (node (ref "LPC-9") (pin "A") (pinfunction "A_A") (pintype "passive"))
      (node (ref "RPC-9") (pin "1") (pinfunction "1_1") (pintype "passive"))
    )
    (net (code "107") (name "Net-(LPC-10-PadA)") (class "Default")
      (node (ref "LPC-10") (pin "A") (pinfunction "A_A") (pintype "passive"))
      (node (ref "RPC-10") (pin "1") (pinfunction "1_1") (pintype "passive"))
    )
    (net (code "108") (name "Net-(LPC-11-PadA)") (class "Default")
      (node (ref "LPC-11") (pin "A") (pinfunction "A_A") (pintype "passive"))
      (node (ref "RPC-11") (pin "1") (pinfunction "1_1") (pintype "passive"))
    )
    (net (code "109") (name "Net-(LPC-12-PadA)") (class "Default")
      (node (ref "LPC-12") (pin "A") (pinfunction "A_A") (pintype "passive"))
      (node (ref "RPC-12") (pin "1") (pinfunction "1_1") (pintype "passive"))
    )
    (net (code "110") (name "Net-(LPR-0-PadA)") (class "Default")
      (node (ref "LPR-0") (pin "A") (pinfunction "A_A") (pintype "passive"))
      (node (ref "RPR-0") (pin "1") (pinfunction "1_1") (pintype "passive"))
    )
    (net (code "111") (name "Net-(LPR-1-PadA)") (class "Default")
      (node (ref "LPR-1") (pin "A") (pinfunction "A_A") (pintype "passive"))
      (node (ref "RPR-1") (pin "1") (pinfunction "1_1") (pintype "passive"))
    )
    (net (code "112") (name "Net-(LPR-2-PadA)") (class "Default")
      (node (ref "LPR-2") (pin "A") (pinfunction "A_A") (pintype "passive"))
      (node (ref "RPR-2") (pin "1") (pinfunction "1_1") (pintype "passive"))
    )
    (net (code "113") (name "Net-(LPR-3-PadA)") (class "Default")
      (node (ref "LPR-3") (pin "A") (pinfunction "A_A") (pintype "passive"))
      (node (ref "RPR-3") (pin "1") (pinfunction "1_1") (pintype "passive"))
    )
    (net (code "114") (name "Net-(LPR-4-PadA)") (class "Default")
      (node (ref "LPR-4") (pin "A") (pinfunction "A_A") (pintype "passive"))
      (node (ref "RPR-4") (pin "1") (pinfunction "1_1") (pintype "passive"))
    )
    (net (code "115") (name "Net-(LPR-5-PadA)") (class "Default")
      (node (ref "LPR-5") (pin "A") (pinfunction "A_A") (pintype "passive"))
      (node (ref "RPR-5") (pin "1") (pinfunction "1_1") (pintype "passive"))
    )
    (net (code "116") (name "Net-(LPR-6-PadA)") (class "Default")
      (node (ref "LPR-6") (pin "A") (pinfunction "A_A") (pintype "passive"))
      (node (ref "RPR-6") (pin "1") (pinfunction "1_1") (pintype "passive"))
    )
    (net (code "117") (name "Net-(LPR-7-PadA)") (class "Default")
      (node (ref "LPR-7") (pin "A") (pinfunction "A_A") (pintype "passive"))
      (node (ref "RPR-7") (pin "1") (pinfunction "1_1") (pintype "passive"))
    )
    (net (code "118") (name "Net-(LPR-8-PadA)") (class "Default")
      (node (ref "LPR-8") (pin "A") (pinfunction "A_A") (pintype "passive"))
      (node (ref "RPR-8") (pin "1") (pinfunction "1_1") (pintype "passive"))
    )
    (net (code "119") (name "Net-(LPR-9-PadA)") (class "Default")
      (node (ref "LPR-9") (pin "A") (pinfunction "A_A") (pintype "passive"))
      (node (ref "RPR-9") (pin "1") (pinfunction "1_1") (pintype "passive"))
    )
    (net (code "120") (name "Net-(LPR-10-PadA)") (class "Default")
      (node (ref "LPR-10") (pin "A") (pinfunction "A_A") (pintype "passive"))
      (node (ref "RPR-10") (pin "1") (pinfunction "1_1") (pintype "passive"))
    )
    (net (code "121") (name "Net-(LPR-11-PadA)") (class "Default")
      (node (ref "LPR-11") (pin "A") (pinfunction "A_A") (pintype "passive"))
      (node (ref "RPR-11") (pin "1") (pinfunction "1_1") (pintype "passive"))
    )
    (net (code "122") (name "Net-(LPR-12-PadA)") (class "Default")
      (node (ref "LPR-12") (pin "A") (pinfunction "A_A") (pintype "passive"))
      (node (ref "RPR-12") (pin "1") (pinfunction "1_1") (pintype "passive"))
    )
    (net (code "123") (name "Net-(LR-0-PadA)") (class "Default")
      (node (ref "LR-0") (pin "A") (pinfunction "A_A") (pintype "passive"))
      (node (ref "RR-0") (pin "1") (pinfunction "1_1") (pintype "passive"))
    )
    (net (code "124") (name "Net-(LR-1-PadA)") (class "Default")
      (node (ref "LR-1") (pin "A") (pinfunction "A_A") (pintype "passive"))
      (node (ref "RR-1") (pin "1") (pinfunction "1_1") (pintype "passive"))
    )
    (net (code "125") (name "Net-(LR-2-PadA)") (class "Default")
      (node (ref "LR-2") (pin "A") (pinfunction "A_A") (pintype "passive"))
      (node (ref "RR-2") (pin "1") (pinfunction "1_1") (pintype "passive"))
    )
    (net (code "126") (name "Net-(LR-3-PadA)") (class "Default")
      (node (ref "LR-3") (pin "A") (pinfunction "A_A") (pintype "passive"))
      (node (ref "RR-3") (pin "1") (pinfunction "1_1") (pintype "passive"))
    )
    (net (code "127") (name "Net-(LR-4-PadA)") (class "Default")
      (node (ref "LR-4") (pin "A") (pinfunction "A_A") (pintype "passive"))
      (node (ref "RR-4") (pin "1") (pinfunction "1_1") (pintype "passive"))
    )
    (net (code "128") (name "Net-(LR-5-PadA)") (class "Default")
      (node (ref "LR-5") (pin "A") (pinfunction "A_A") (pintype "passive"))
      (node (ref "RR-5") (pin "1") (pinfunction "1_1") (pintype "passive"))
    )
    (net (code "129") (name "Net-(LR-6-PadA)") (class "Default")
      (node (ref "LR-6") (pin "A") (pinfunction "A_A") (pintype "passive"))
      (node (ref "RR-6") (pin "1") (pinfunction "1_1") (pintype "passive"))
    )
    (net (code "130") (name "Net-(LR-7-PadA)") (class "Default")
      (node (ref "LR-7") (pin "A") (pinfunction "A_A") (pintype "passive"))
      (node (ref "RR-7") (pin "1") (pinfunction "1_1") (pintype "passive"))
    )
    (net (code "131") (name "Net-(LT-0-PadA)") (class "Default")
      (node (ref "LT-0") (pin "A") (pinfunction "A_A") (pintype "passive"))
      (node (ref "RT-0") (pin "1") (pinfunction "1_1") (pintype "passive"))
    )
    (net (code "132") (name "Net-(LT-1-PadA)") (class "Default")
      (node (ref "LT-1") (pin "A") (pinfunction "A_A") (pintype "passive"))
      (node (ref "RT-1") (pin "1") (pinfunction "1_1") (pintype "passive"))
    )
    (net (code "133") (name "Net-(LT-2-PadA)") (class "Default")
      (node (ref "LT-2") (pin "A") (pinfunction "A_A") (pintype "passive"))
      (node (ref "RT-2") (pin "1") (pinfunction "1_1") (pintype "passive"))
    )
    (net (code "134") (name "Net-(LT-3-PadA)") (class "Default")
      (node (ref "LT-3") (pin "A") (pinfunction "A_A") (pintype "passive"))
      (node (ref "RT-3") (pin "1") (pinfunction "1_1") (pintype "passive"))
    )
    (net (code "135") (name "Net-(LT-4-PadA)") (class "Default")
      (node (ref "LT-4") (pin "A") (pinfunction "A_A") (pintype "passive"))
      (node (ref "RT-4") (pin "1") (pinfunction "1_1") (pintype "passive"))
    )
    (net (code "136") (name "Net-(LT-5-PadA)") (class "Default")
      (node (ref "LT-5") (pin "A") (pinfunction "A_A") (pintype "passive"))
      (node (ref "RT-5") (pin "1") (pinfunction "1_1") (pintype "passive"))
    )
    (net (code "137") (name "Net-(LT-6-PadA)") (class "Default")
      (node (ref "LT-6") (pin "A") (pinfunction "A_A") (pintype "passive"))
      (node (ref "RT-6") (pin "1") (pinfunction "1_1") (pintype "passive"))
    )
    (net (code "138") (name "Net-(LT-7-PadA)") (class "Default")
      (node (ref "LT-7") (pin "A") (pinfunction "A_A") (pintype "passive"))
      (node (ref "RT-7") (pin "1") (pinfunction "1_1") (pintype "passive"))
    )
    (net (code "139") (name "Net-(LX-0-PadA)") (class "Default")
      (node (ref "LX-0") (pin "A") (pinfunction "A_A") (pintype "passive"))
      (node (ref "RX-0") (pin "1") (pinfunction "1_1") (pintype "passive"))
    )
    (net (code "140") (name "Net-(LX-1-PadA)") (class "Default")
      (node (ref "LX-1") (pin "A") (pinfunction "A_A") (pintype "passive"))
      (node (ref "RX-1") (pin "1") (pinfunction "1_1") (pintype "passive"))
    )
    (net (code "141") (name "Net-(LX-2-PadA)") (class "Default")
      (node (ref "LX-2") (pin "A") (pinfunction "A_A") (pintype "passive"))
      (node (ref "RX-2") (pin "1") (pinfunction "1_1") (pintype "passive"))
    )
    (net (code "142") (name "Net-(LX-3-PadA)") (class "Default")
      (node (ref "LX-3") (pin "A") (pinfunction "A_A") (pintype "passive"))
      (node (ref "RX-3") (pin "1") (pinfunction "1_1") (pintype "passive"))
    )
    (net (code "143") (name "Net-(LX-4-PadA)") (class "Default")
      (node (ref "LX-4") (pin "A") (pinfunction "A_A") (pintype "passive"))
      (node (ref "RX-4") (pin "1") (pinfunction "1_1") (pintype "passive"))
    )
    (net (code "144") (name "Net-(LX-5-PadA)") (class "Default")
      (node (ref "LX-5") (pin "A") (pinfunction "A_A") (pintype "passive"))
      (node (ref "RX-5") (pin "1") (pinfunction "1_1") (pintype "passive"))
    )
    (net (code "145") (name "Net-(LX-6-PadA)") (class "Default")
      (node (ref "LX-6") (pin "A") (pinfunction "A_A") (pintype "passive"))
      (node (ref "RX-6") (pin "1") (pinfunction "1_1") (pintype "passive"))
    )
    (net (code "146") (name "Net-(LX-7-PadA)") (class "Default")
      (node (ref "LX-7") (pin "A") (pinfunction "A_A") (pintype "passive"))
      (node (ref "RX-7") (pin "1") (pinfunction "1_1") (pintype "passive"))
    )
    (net (code "147") (name "Net-(LX-8-PadA)") (class "Default")
      (node (ref "LX-8") (pin "A") (pinfunction "A_A") (pintype "passive"))
      (node (ref "RX-8") (pin "1") (pinfunction "1_1") (pintype "passive"))
    )
    (net (code "148") (name "Net-(LXO-0-PadA)") (class "Default")
      (node (ref "LXO-0") (pin "A") (pinfunction "A_A") (pintype "passive"))
      (node (ref "RXO-0") (pin "1") (pinfunction "1_1") (pintype "passive"))
    )
    (net (code "149") (name "Net-(LXO-1-PadA)") (class "Default")
      (node (ref "LXO-1") (pin "A") (pinfunction "A_A") (pintype "passive"))
      (node (ref "RXO-1") (pin "1") (pinfunction "1_1") (pintype "passive"))
    )
    (net (code "150") (name "Net-(LXO-2-PadA)") (class "Default")
      (node (ref "LXO-2") (pin "A") (pinfunction "A_A") (pintype "passive"))
      (node (ref "RXO-2") (pin "1") (pinfunction "1_1") (pintype "passive"))
    )
    (net (code "151") (name "Net-(LXO-3-PadA)") (class "Default")
      (node (ref "LXO-3") (pin "A") (pinfunction "A_A") (pintype "passive"))
      (node (ref "RXO-3") (pin "1") (pinfunction "1_1") (pintype "passive"))
    )
    (net (code "152") (name "Net-(LXO-4-PadA)") (class "Default")
      (node (ref "LXO-4") (pin "A") (pinfunction "A_A") (pintype "passive"))
      (node (ref "RXO-4") (pin "1") (pinfunction "1_1") (pintype "passive"))
    )
    (net (code "153") (name "Net-(LXO-5-PadA)") (class "Default")
      (node (ref "LXO-5") (pin "A") (pinfunction "A_A") (pintype "passive"))
      (node (ref "RXO-5") (pin "1") (pinfunction "1_1") (pintype "passive"))
    )
    (net (code "154") (name "Net-(LXO-6-PadA)") (class "Default")
      (node (ref "LXO-6") (pin "A") (pinfunction "A_A") (pintype "passive"))
      (node (ref "RXO-6") (pin "1") (pinfunction "1_1") (pintype "passive"))
    )
    (net (code "155") (name "Net-(LXO-7-PadA)") (class "Default")
      (node (ref "LXO-7") (pin "A") (pinfunction "A_A") (pintype "passive"))
      (node (ref "RXO-7") (pin "1") (pinfunction "1_1") (pintype "passive"))
    )
    (net (code "156") (name "Net-(LY-0-PadA)") (class "Default")
      (node (ref "LY-0") (pin "A") (pinfunction "A_A") (pintype "passive"))
      (node (ref "RY-0") (pin "1") (pinfunction "1_1") (pintype "passive"))
    )
    (net (code "157") (name "Net-(LY-1-PadA)") (class "Default")
      (node (ref "LY-1") (pin "A") (pinfunction "A_A") (pintype "passive"))
      (node (ref "RY-1") (pin "1") (pinfunction "1_1") (pintype "passive"))
    )
    (net (code "158") (name "Net-(LY-2-PadA)") (class "Default")
      (node (ref "LY-2") (pin "A") (pinfunction "A_A") (pintype "passive"))
      (node (ref "RY-2") (pin "1") (pinfunction "1_1") (pintype "passive"))
    )
    (net (code "159") (name "Net-(LY-3-PadA)") (class "Default")
      (node (ref "LY-3") (pin "A") (pinfunction "A_A") (pintype "passive"))
      (node (ref "RY-3") (pin "1") (pinfunction "1_1") (pintype "passive"))
    )
    (net (code "160") (name "Net-(LY-4-PadA)") (class "Default")
      (node (ref "LY-4") (pin "A") (pinfunction "A_A") (pintype "passive"))
      (node (ref "RY-4") (pin "1") (pinfunction "1_1") (pintype "passive"))
    )
    (net (code "161") (name "Net-(LY-5-PadA)") (class "Default")
      (node (ref "LY-5") (pin "A") (pinfunction "A_A") (pintype "passive"))
      (node (ref "RY-5") (pin "1") (pinfunction "1_1") (pintype "passive"))
    )
    (net (code "162") (name "Net-(LY-6-PadA)") (class "Default")
      (node (ref "LY-6") (pin "A") (pinfunction "A_A") (pintype "passive"))
      (node (ref "RY-6") (pin "1") (pinfunction "1_1") (pintype "passive"))
    )
    (net (code "163") (name "Net-(LY-7-PadA)") (class "Default")
      (node (ref "LY-7") (pin "A") (pinfunction "A_A") (pintype "passive"))
      (node (ref "RY-7") (pin "1") (pinfunction "1_1") (pintype "passive"))
    )
    (net (code "164") (name "Net-(PC0C-CLR)") (class "Default")
      (node (ref "PC0") (pin "14") (pinfunction "CLR_14") (pintype "input"))
      (node (ref "PC1") (pin "14") (pinfunction "CLR_14") (pintype "input"))
      (node (ref "PC2") (pin "14") (pinfunction "CLR_14") (pintype "input"))
      (node (ref "PC3") (pin "14") (pinfunction "CLR_14") (pintype "input"))
    )
    (net (code "165") (name "Net-(PC0C-~{CO})") (class "Default")
      (node (ref "PC0") (pin "12") (pinfunction "~{CO}_12") (pintype "output"))
      (node (ref "PC1") (pin "5") (pinfunction "UP_5") (pintype "input"))
    )
    (net (code "166") (name "Net-(PC1C-~{CO})") (class "Default")
      (node (ref "PC1") (pin "12") (pinfunction "~{CO}_12") (pintype "output"))
      (node (ref "PC2") (pin "5") (pinfunction "UP_5") (pintype "input"))
    )
    (net (code "167") (name "Net-(PC2C-~{CO})") (class "Default")
      (node (ref "PC2") (pin "12") (pinfunction "~{CO}_12") (pintype "output"))
      (node (ref "PC3") (pin "5") (pinfunction "UP_5") (pintype "input"))
    )
    (net (code "168") (name "Net-(ZHC-A)") (class "Default")
      (node (ref "ZH") (pin "1") (pinfunction "A_1") (pintype "input"))
      (node (ref "ZL") (pin "1") (pinfunction "Y_1") (pintype "output"))
    )
    (net (code "169") (name "Net-(ZHC-B)") (class "Default")
      (node (ref "ZH") (pin "2") (pinfunction "B_2") (pintype "input"))
      (node (ref "ZL") (pin "4") (pinfunction "Y_4") (pintype "output"))
    )
    (net (code "170") (name "Net-(ZHC-Y)") (class "Default")
      (node (ref "ZH") (pin "3") (pinfunction "Y_3") (pintype "output"))
      (node (ref "ZH") (pin "9") (pinfunction "A_9") (pintype "input"))
    )
    (net (code "171") (name "Net-(ZHD-A)") (class "Default")
      (node (ref "ZH") (pin "4") (pinfunction "A_4") (pintype "input"))
      (node (ref "ZL") (pin "10") (pinfunction "Y_10") (pintype "output"))
    )
    (net (code "172") (name "Net-(ZHD-B)") (class "Default")
      (node (ref "ZH") (pin "5") (pinfunction "B_5") (pintype "input"))
      (node (ref "ZL") (pin "13") (pinfunction "Y_13") (pintype "output"))
    )
    (net (code "173") (name "Net-(ZHD-Y)") (class "Default")
      (node (ref "ZH") (pin "10") (pinfunction "B_10") (pintype "input"))
      (node (ref "ZH") (pin "6") (pinfunction "Y_6") (pintype "output"))
    )
    (net (code "174") (name "OF") (class "Default")
      (node (ref "AH") (pin "9") (pinfunction "C4_9") (pintype "output"))
      (node (ref "ROF") (pin "2") (pinfunction "2_2") (pintype "passive"))
    )
    (net (code "175") (name "OP") (class "Default")
      (node (ref "PC3") (pin "2") (pinfunction "QB_2") (pintype "output"))
    )
    (net (code "176") (name "OR-B") (class "Default")
      (node (ref "ORB") (pin "19") (pinfunction "~{G}_19") (pintype "input"))
    )
    (net (code "177") (name "OR0") (class "Default")
      (node (ref "ORB") (pin "2") (pinfunction "A1_2") (pintype "bidirectional"))
      (node (ref "ORL") (pin "3") (pinfunction "Y_3") (pintype "output"))
      (node (ref "ROR-0") (pin "2") (pinfunction "2_2") (pintype "passive"))
    )
    (net (code "178") (name "OR1") (class "Default")
      (node (ref "ORB") (pin "3") (pinfunction "A2_3") (pintype "bidirectional"))
      (node (ref "ORL") (pin "6") (pinfunction "Y_6") (pintype "output"))
      (node (ref "ROR-1") (pin "2") (pinfunction "2_2") (pintype "passive"))
    )
    (net (code "179") (name "OR2") (class "Default")
      (node (ref "ORB") (pin "4") (pinfunction "A3_4") (pintype "bidirectional"))
      (node (ref "ORL") (pin "8") (pinfunction "Y_8") (pintype "output"))
      (node (ref "ROR-2") (pin "2") (pinfunction "2_2") (pintype "passive"))
    )
    (net (code "180") (name "OR3") (class "Default")
      (node (ref "ORB") (pin "5") (pinfunction "A4_5") (pintype "bidirectional"))
      (node (ref "ORL") (pin "11") (pinfunction "Y_11") (pintype "output"))
      (node (ref "ROR-3") (pin "2") (pinfunction "2_2") (pintype "passive"))
    )
    (net (code "181") (name "OR4") (class "Default")
      (node (ref "ORB") (pin "6") (pinfunction "A5_6") (pintype "bidirectional"))
      (node (ref "ORH") (pin "3") (pinfunction "Y_3") (pintype "output"))
      (node (ref "ROR-4") (pin "2") (pinfunction "2_2") (pintype "passive"))
    )
    (net (code "182") (name "OR5") (class "Default")
      (node (ref "ORB") (pin "7") (pinfunction "A6_7") (pintype "bidirectional"))
      (node (ref "ORH") (pin "6") (pinfunction "Y_6") (pintype "output"))
      (node (ref "ROR-5") (pin "2") (pinfunction "2_2") (pintype "passive"))
    )
    (net (code "183") (name "OR6") (class "Default")
      (node (ref "ORB") (pin "8") (pinfunction "A7_8") (pintype "bidirectional"))
      (node (ref "ORH") (pin "8") (pinfunction "Y_8") (pintype "output"))
      (node (ref "ROR-6") (pin "2") (pinfunction "2_2") (pintype "passive"))
    )
    (net (code "184") (name "OR7") (class "Default")
      (node (ref "ORB") (pin "9") (pinfunction "A8_9") (pintype "bidirectional"))
      (node (ref "ORH") (pin "11") (pinfunction "Y_11") (pintype "output"))
      (node (ref "ROR-7") (pin "2") (pinfunction "2_2") (pintype "passive"))
    )
    (net (code "185") (name "PC0") (class "Default")
      (node (ref "PC0") (pin "3") (pinfunction "QA_3") (pintype "output"))
      (node (ref "PL-S") (pin "2") (pinfunction "A1_2") (pintype "bidirectional"))
      (node (ref "ROM") (pin "10") (pinfunction "A0_10") (pintype "input"))
      (node (ref "RPC-0") (pin "2") (pinfunction "2_2") (pintype "passive"))
    )
    (net (code "186") (name "PC1") (class "Default")
      (node (ref "PC0") (pin "2") (pinfunction "QB_2") (pintype "output"))
      (node (ref "PL-S") (pin "3") (pinfunction "A2_3") (pintype "bidirectional"))
      (node (ref "ROM") (pin "9") (pinfunction "A1_9") (pintype "input"))
      (node (ref "RPC-1") (pin "2") (pinfunction "2_2") (pintype "passive"))
    )
    (net (code "187") (name "PC2") (class "Default")
      (node (ref "PC0") (pin "6") (pinfunction "QC_6") (pintype "output"))
      (node (ref "PL-S") (pin "4") (pinfunction "A3_4") (pintype "bidirectional"))
      (node (ref "ROM") (pin "8") (pinfunction "A2_8") (pintype "input"))
      (node (ref "RPC-2") (pin "2") (pinfunction "2_2") (pintype "passive"))
    )
    (net (code "188") (name "PC3") (class "Default")
      (node (ref "PC0") (pin "7") (pinfunction "QD_7") (pintype "output"))
      (node (ref "PL-S") (pin "5") (pinfunction "A4_5") (pintype "bidirectional"))
      (node (ref "ROM") (pin "7") (pinfunction "A3_7") (pintype "input"))
      (node (ref "RPC-3") (pin "2") (pinfunction "2_2") (pintype "passive"))
    )
    (net (code "189") (name "PC4") (class "Default")
      (node (ref "PC1") (pin "3") (pinfunction "QA_3") (pintype "output"))
      (node (ref "PL-S") (pin "6") (pinfunction "A5_6") (pintype "bidirectional"))
      (node (ref "ROM") (pin "6") (pinfunction "A4_6") (pintype "input"))
      (node (ref "RPC-4") (pin "2") (pinfunction "2_2") (pintype "passive"))
    )
    (net (code "190") (name "PC5") (class "Default")
      (node (ref "PC1") (pin "2") (pinfunction "QB_2") (pintype "output"))
      (node (ref "PL-S") (pin "7") (pinfunction "A6_7") (pintype "bidirectional"))
      (node (ref "ROM") (pin "5") (pinfunction "A5_5") (pintype "input"))
      (node (ref "RPC-5") (pin "2") (pinfunction "2_2") (pintype "passive"))
    )
    (net (code "191") (name "PC6") (class "Default")
      (node (ref "PC1") (pin "6") (pinfunction "QC_6") (pintype "output"))
      (node (ref "PL-S") (pin "8") (pinfunction "A7_8") (pintype "bidirectional"))
      (node (ref "ROM") (pin "4") (pinfunction "A6_4") (pintype "input"))
      (node (ref "RPC-6") (pin "2") (pinfunction "2_2") (pintype "passive"))
    )
    (net (code "192") (name "PC7") (class "Default")
      (node (ref "PC1") (pin "7") (pinfunction "QD_7") (pintype "output"))
      (node (ref "PL-S") (pin "9") (pinfunction "A8_9") (pintype "bidirectional"))
      (node (ref "ROM") (pin "3") (pinfunction "A7_3") (pintype "input"))
      (node (ref "RPC-7") (pin "2") (pinfunction "2_2") (pintype "passive"))
    )
    (net (code "193") (name "PC8") (class "Default")
      (node (ref "PC2") (pin "3") (pinfunction "QA_3") (pintype "output"))
      (node (ref "PH-S") (pin "2") (pinfunction "A1_2") (pintype "bidirectional"))
      (node (ref "ROM") (pin "25") (pinfunction "A8_25") (pintype "input"))
      (node (ref "RPC-8") (pin "2") (pinfunction "2_2") (pintype "passive"))
    )
    (net (code "194") (name "PC9") (class "Default")
      (node (ref "PC2") (pin "2") (pinfunction "QB_2") (pintype "output"))
      (node (ref "PH-S") (pin "3") (pinfunction "A2_3") (pintype "bidirectional"))
      (node (ref "ROM") (pin "24") (pinfunction "A9_24") (pintype "input"))
      (node (ref "RPC-9") (pin "2") (pinfunction "2_2") (pintype "passive"))
    )
    (net (code "195") (name "PC10") (class "Default")
      (node (ref "PC2") (pin "6") (pinfunction "QC_6") (pintype "output"))
      (node (ref "PH-S") (pin "4") (pinfunction "A3_4") (pintype "bidirectional"))
      (node (ref "ROM") (pin "21") (pinfunction "A10_21") (pintype "input"))
      (node (ref "RPC-10") (pin "2") (pinfunction "2_2") (pintype "passive"))
    )
    (net (code "196") (name "PC11") (class "Default")
      (node (ref "PC2") (pin "7") (pinfunction "QD_7") (pintype "output"))
      (node (ref "PH-S") (pin "5") (pinfunction "A4_5") (pintype "bidirectional"))
      (node (ref "ROM") (pin "23") (pinfunction "A11_23") (pintype "input"))
      (node (ref "RPC-11") (pin "2") (pinfunction "2_2") (pintype "passive"))
    )
    (net (code "197") (name "PC12") (class "Default")
      (node (ref "PC3") (pin "3") (pinfunction "QA_3") (pintype "output"))
      (node (ref "PH-S") (pin "6") (pinfunction "A5_6") (pintype "bidirectional"))
      (node (ref "ROM") (pin "2") (pinfunction "A12_2") (pintype "input"))
      (node (ref "RPC-12") (pin "2") (pinfunction "2_2") (pintype "passive"))
    )
    (net (code "198") (name "PH-B") (class "Default")
      (node (ref "PH-S") (pin "19") (pinfunction "~{G}_19") (pintype "input"))
    )
    (net (code "199") (name "PL-B") (class "Default")
      (node (ref "PL-S") (pin "19") (pinfunction "~{G}_19") (pintype "input"))
    )
    (net (code "200") (name "PR-H") (class "Default")
      (node (ref "PR-H") (pin "11") (pinfunction "CLK_11") (pintype "input"))
    )
    (net (code "201") (name "PR-L") (class "Default")
      (node (ref "PR-L") (pin "11") (pinfunction "CLK_11") (pintype "input"))
    )
    (net (code "202") (name "PR0") (class "Default")
      (node (ref "PC0") (pin "15") (pinfunction "A_15") (pintype "input"))
      (node (ref "PR-L") (pin "2") (pinfunction "1Q_2") (pintype "output"))
      (node (ref "RPR-0") (pin "2") (pinfunction "2_2") (pintype "passive"))
    )
    (net (code "203") (name "PR1") (class "Default")
      (node (ref "PC0") (pin "1") (pinfunction "B_1") (pintype "input"))
      (node (ref "PR-L") (pin "5") (pinfunction "2Q_5") (pintype "output"))
      (node (ref "RPR-1") (pin "2") (pinfunction "2_2") (pintype "passive"))
    )
    (net (code "204") (name "PR2") (class "Default")
      (node (ref "PC0") (pin "10") (pinfunction "C_10") (pintype "input"))
      (node (ref "PR-L") (pin "6") (pinfunction "3Q_6") (pintype "output"))
      (node (ref "RPR-2") (pin "2") (pinfunction "2_2") (pintype "passive"))
    )
    (net (code "205") (name "PR3") (class "Default")
      (node (ref "PC0") (pin "9") (pinfunction "D_9") (pintype "input"))
      (node (ref "PR-L") (pin "9") (pinfunction "4Q_9") (pintype "output"))
      (node (ref "RPR-3") (pin "2") (pinfunction "2_2") (pintype "passive"))
    )
    (net (code "206") (name "PR4") (class "Default")
      (node (ref "PC1") (pin "15") (pinfunction "A_15") (pintype "input"))
      (node (ref "PR-L") (pin "12") (pinfunction "5Q_12") (pintype "output"))
      (node (ref "RPR-4") (pin "2") (pinfunction "2_2") (pintype "passive"))
    )
    (net (code "207") (name "PR5") (class "Default")
      (node (ref "PC1") (pin "1") (pinfunction "B_1") (pintype "input"))
      (node (ref "PR-L") (pin "15") (pinfunction "6Q_15") (pintype "output"))
      (node (ref "RPR-5") (pin "2") (pinfunction "2_2") (pintype "passive"))
    )
    (net (code "208") (name "PR6") (class "Default")
      (node (ref "PC1") (pin "10") (pinfunction "C_10") (pintype "input"))
      (node (ref "PR-L") (pin "16") (pinfunction "7Q_16") (pintype "output"))
      (node (ref "RPR-6") (pin "2") (pinfunction "2_2") (pintype "passive"))
    )
    (net (code "209") (name "PR7") (class "Default")
      (node (ref "PC1") (pin "9") (pinfunction "D_9") (pintype "input"))
      (node (ref "PR-L") (pin "19") (pinfunction "8Q_19") (pintype "output"))
      (node (ref "RPR-7") (pin "2") (pinfunction "2_2") (pintype "passive"))
    )
    (net (code "210") (name "PR8") (class "Default")
      (node (ref "PC2") (pin "15") (pinfunction "A_15") (pintype "input"))
      (node (ref "PR-H") (pin "2") (pinfunction "1Q_2") (pintype "output"))
      (node (ref "RPR-8") (pin "2") (pinfunction "2_2") (pintype "passive"))
    )
    (net (code "211") (name "PR9") (class "Default")
      (node (ref "PC2") (pin "1") (pinfunction "B_1") (pintype "input"))
      (node (ref "PR-H") (pin "5") (pinfunction "2Q_5") (pintype "output"))
      (node (ref "RPR-9") (pin "2") (pinfunction "2_2") (pintype "passive"))
    )
    (net (code "212") (name "PR10") (class "Default")
      (node (ref "PC2") (pin "10") (pinfunction "C_10") (pintype "input"))
      (node (ref "PR-H") (pin "6") (pinfunction "3Q_6") (pintype "output"))
      (node (ref "RPR-10") (pin "2") (pinfunction "2_2") (pintype "passive"))
    )
    (net (code "213") (name "PR11") (class "Default")
      (node (ref "PC2") (pin "9") (pinfunction "D_9") (pintype "input"))
      (node (ref "PR-H") (pin "9") (pinfunction "4Q_9") (pintype "output"))
      (node (ref "RPR-11") (pin "2") (pinfunction "2_2") (pintype "passive"))
    )
    (net (code "214") (name "PR12") (class "Default")
      (node (ref "PC3") (pin "15") (pinfunction "A_15") (pintype "input"))
      (node (ref "PR-H") (pin "12") (pinfunction "5Q_12") (pintype "output"))
      (node (ref "RPR-12") (pin "2") (pinfunction "2_2") (pintype "passive"))
    )
    (net (code "215") (name "R0") (class "Default")
      (node (ref "ROM") (pin "11") (pinfunction "I/O0_11") (pintype "bidirectional"))
      (node (ref "ROM-B") (pin "2") (pinfunction "A1_2") (pintype "bidirectional"))
      (node (ref "RR-0") (pin "2") (pinfunction "2_2") (pintype "passive"))
    )
    (net (code "216") (name "R1") (class "Default")
      (node (ref "ROM") (pin "12") (pinfunction "I/O1_12") (pintype "bidirectional"))
      (node (ref "ROM-B") (pin "3") (pinfunction "A2_3") (pintype "bidirectional"))
      (node (ref "RR-1") (pin "2") (pinfunction "2_2") (pintype "passive"))
    )
    (net (code "217") (name "R2") (class "Default")
      (node (ref "ROM") (pin "13") (pinfunction "I/O2_13") (pintype "bidirectional"))
      (node (ref "ROM-B") (pin "4") (pinfunction "A3_4") (pintype "bidirectional"))
      (node (ref "RR-2") (pin "2") (pinfunction "2_2") (pintype "passive"))
    )
    (net (code "218") (name "R3") (class "Default")
      (node (ref "ROM") (pin "15") (pinfunction "I/O3_15") (pintype "bidirectional"))
      (node (ref "ROM-B") (pin "5") (pinfunction "A4_5") (pintype "bidirectional"))
      (node (ref "RR-3") (pin "2") (pinfunction "2_2") (pintype "passive"))
    )
    (net (code "219") (name "R4") (class "Default")
      (node (ref "ROM") (pin "16") (pinfunction "I/O4_16") (pintype "bidirectional"))
      (node (ref "ROM-B") (pin "6") (pinfunction "A5_6") (pintype "bidirectional"))
      (node (ref "RR-4") (pin "2") (pinfunction "2_2") (pintype "passive"))
    )
    (net (code "220") (name "R5") (class "Default")
      (node (ref "ROM") (pin "17") (pinfunction "I/O5_17") (pintype "bidirectional"))
      (node (ref "ROM-B") (pin "7") (pinfunction "A6_7") (pintype "bidirectional"))
      (node (ref "RR-5") (pin "2") (pinfunction "2_2") (pintype "passive"))
    )
    (net (code "221") (name "R6") (class "Default")
      (node (ref "ROM") (pin "18") (pinfunction "I/O6_18") (pintype "bidirectional"))
      (node (ref "ROM-B") (pin "8") (pinfunction "A7_8") (pintype "bidirectional"))
      (node (ref "RR-6") (pin "2") (pinfunction "2_2") (pintype "passive"))
    )
    (net (code "222") (name "R7") (class "Default")
      (node (ref "ROM") (pin "19") (pinfunction "I/O7_19") (pintype "bidirectional"))
      (node (ref "ROM-B") (pin "9") (pinfunction "A8_9") (pintype "bidirectional"))
      (node (ref "RR-7") (pin "2") (pinfunction "2_2") (pintype "passive"))
    )
    (net (code "223") (name "ROM-B") (class "Default")
      (node (ref "ROM-B") (pin "19") (pinfunction "~{G}_19") (pintype "input"))
    )
    (net (code "224") (name "T0") (class "Default")
      (node (ref "AL") (pin "6") (pinfunction "B1_6") (pintype "input"))
      (node (ref "RT-0") (pin "2") (pinfunction "2_2") (pintype "passive"))
      (node (ref "TL") (pin "3") (pinfunction "Y_3") (pintype "output"))
    )
    (net (code "225") (name "T1") (class "Default")
      (node (ref "AL") (pin "2") (pinfunction "B2_2") (pintype "input"))
      (node (ref "RT-1") (pin "2") (pinfunction "2_2") (pintype "passive"))
      (node (ref "TL") (pin "6") (pinfunction "Y_6") (pintype "output"))
    )
    (net (code "226") (name "T2") (class "Default")
      (node (ref "AL") (pin "15") (pinfunction "B3_15") (pintype "input"))
      (node (ref "RT-2") (pin "2") (pinfunction "2_2") (pintype "passive"))
      (node (ref "TL") (pin "8") (pinfunction "Y_8") (pintype "output"))
    )
    (net (code "227") (name "T3") (class "Default")
      (node (ref "AL") (pin "11") (pinfunction "B4_11") (pintype "input"))
      (node (ref "RT-3") (pin "2") (pinfunction "2_2") (pintype "passive"))
      (node (ref "TL") (pin "11") (pinfunction "Y_11") (pintype "output"))
    )
    (net (code "228") (name "T4") (class "Default")
      (node (ref "AH") (pin "6") (pinfunction "B1_6") (pintype "input"))
      (node (ref "RT-4") (pin "2") (pinfunction "2_2") (pintype "passive"))
      (node (ref "TH") (pin "3") (pinfunction "Y_3") (pintype "output"))
    )
    (net (code "229") (name "T5") (class "Default")
      (node (ref "AH") (pin "2") (pinfunction "B2_2") (pintype "input"))
      (node (ref "RT-5") (pin "2") (pinfunction "2_2") (pintype "passive"))
      (node (ref "TH") (pin "6") (pinfunction "Y_6") (pintype "output"))
    )
    (net (code "230") (name "T6") (class "Default")
      (node (ref "AH") (pin "15") (pinfunction "B3_15") (pintype "input"))
      (node (ref "RT-6") (pin "2") (pinfunction "2_2") (pintype "passive"))
      (node (ref "TH") (pin "8") (pinfunction "Y_8") (pintype "output"))
    )
    (net (code "231") (name "T7") (class "Default")
      (node (ref "AH") (pin "11") (pinfunction "B4_11") (pintype "input"))
      (node (ref "RT-7") (pin "2") (pinfunction "2_2") (pintype "passive"))
      (node (ref "TH") (pin "11") (pinfunction "Y_11") (pintype "output"))
    )
    (net (code "232") (name "VCC") (class "Default")
      (node (ref "A") (pin "1") (pinfunction "~{CLR}_1") (pintype "input"))
      (node (ref "A") (pin "20") (pinfunction "+UB_20") (pintype "power_in"))
      (node (ref "AB") (pin "1") (pinfunction "DIR_1") (pintype "input"))
      (node (ref "AB") (pin "20") (pinfunction "+UB_20") (pintype "power_in"))
      (node (ref "AH") (pin "16") (pinfunction "+UB_16") (pintype "power_in"))
      (node (ref "AL") (pin "16") (pinfunction "+UB_16") (pintype "power_in"))
      (node (ref "ANB") (pin "1") (pinfunction "DIR_1") (pintype "input"))
      (node (ref "ANB") (pin "20") (pinfunction "+UB_20") (pintype "power_in"))
      (node (ref "ANH") (pin "14") (pinfunction "+UB_14") (pintype "power_in"))
      (node (ref "ANL") (pin "14") (pinfunction "+UB_14") (pintype "power_in"))
      (node (ref "ASB") (pin "1") (pinfunction "DIR_1") (pintype "input"))
      (node (ref "ASB") (pin "20") (pinfunction "+UB_20") (pintype "power_in"))
      (node (ref "NOB") (pin "1") (pinfunction "DIR_1") (pintype "input"))
      (node (ref "NOB") (pin "20") (pinfunction "+UB_20") (pintype "power_in"))
      (node (ref "NOH") (pin "14") (pinfunction "+UB_14") (pintype "power_in"))
      (node (ref "NOL") (pin "14") (pinfunction "+UB_14") (pintype "power_in"))
      (node (ref "ORB") (pin "1") (pinfunction "DIR_1") (pintype "input"))
      (node (ref "ORB") (pin "20") (pinfunction "+UB_20") (pintype "power_in"))
      (node (ref "ORH") (pin "14") (pinfunction "+UB_14") (pintype "power_in"))
      (node (ref "ORL") (pin "14") (pinfunction "+UB_14") (pintype "power_in"))
      (node (ref "PC0") (pin "16") (pinfunction "+UB_16") (pintype "power_in"))
      (node (ref "PC0") (pin "4") (pinfunction "DOWN_4") (pintype "input"))
      (node (ref "PC1") (pin "16") (pinfunction "+UB_16") (pintype "power_in"))
      (node (ref "PC1") (pin "4") (pinfunction "DOWN_4") (pintype "input"))
      (node (ref "PC2") (pin "16") (pinfunction "+UB_16") (pintype "power_in"))
      (node (ref "PC2") (pin "4") (pinfunction "DOWN_4") (pintype "input"))
      (node (ref "PC3") (pin "16") (pinfunction "+UB_16") (pintype "power_in"))
      (node (ref "PC3") (pin "4") (pinfunction "DOWN_4") (pintype "input"))
      (node (ref "PH-S") (pin "20") (pinfunction "+UB_20") (pintype "power_in"))
      (node (ref "PL-S") (pin "20") (pinfunction "+UB_20") (pintype "power_in"))
      (node (ref "PR-H") (pin "1") (pinfunction "~{CLR}_1") (pintype "input"))
      (node (ref "PR-H") (pin "20") (pinfunction "+UB_20") (pintype "power_in"))
      (node (ref "PR-L") (pin "1") (pinfunction "~{CLR}_1") (pintype "input"))
      (node (ref "PR-L") (pin "20") (pinfunction "+UB_20") (pintype "power_in"))
      (node (ref "ROM") (pin "28") (pinfunction "VCC_28") (pintype "power_in"))
      (node (ref "ROM-B") (pin "1") (pinfunction "DIR_1") (pintype "input"))
      (node (ref "ROM-B") (pin "20") (pinfunction "+UB_20") (pintype "power_in"))
      (node (ref "TH") (pin "14") (pinfunction "+UB_14") (pintype "power_in"))
      (node (ref "TL") (pin "14") (pinfunction "+UB_14") (pintype "power_in"))
      (node (ref "X") (pin "1") (pinfunction "~{CLR}_1") (pintype "input"))
      (node (ref "X") (pin "20") (pinfunction "+UB_20") (pintype "power_in"))
      (node (ref "XB") (pin "1") (pinfunction "DIR_1") (pintype "input"))
      (node (ref "XB") (pin "20") (pinfunction "+UB_20") (pintype "power_in"))
      (node (ref "XOB") (pin "1") (pinfunction "DIR_1") (pintype "input"))
      (node (ref "XOB") (pin "20") (pinfunction "+UB_20") (pintype "power_in"))
      (node (ref "XOH") (pin "14") (pinfunction "+UB_14") (pintype "power_in"))
      (node (ref "XOL") (pin "14") (pinfunction "+UB_14") (pintype "power_in"))
      (node (ref "Y") (pin "1") (pinfunction "~{CLR}_1") (pintype "input"))
      (node (ref "Y") (pin "20") (pinfunction "+UB_20") (pintype "power_in"))
      (node (ref "YB") (pin "1") (pinfunction "DIR_1") (pintype "input"))
      (node (ref "YB") (pin "20") (pinfunction "+UB_20") (pintype "power_in"))
      (node (ref "ZH") (pin "14") (pinfunction "+UB_14") (pintype "power_in"))
      (node (ref "ZL") (pin "14") (pinfunction "+UB_14") (pintype "power_in"))
    )
    (net (code "233") (name "X-B") (class "Default")
      (node (ref "XB") (pin "19") (pinfunction "~{G}_19") (pintype "input"))
    )
    (net (code "234") (name "X-C") (class "Default")
      (node (ref "X") (pin "11") (pinfunction "CLK_11") (pintype "input"))
    )
    (net (code "235") (name "X0") (class "Default")
      (node (ref "RX-0") (pin "2") (pinfunction "2_2") (pintype "passive"))
      (node (ref "X") (pin "2") (pinfunction "1Q_2") (pintype "output"))
      (node (ref "XB") (pin "2") (pinfunction "A1_2") (pintype "bidirectional"))
    )
    (net (code "236") (name "X1") (class "Default")
      (node (ref "RX-1") (pin "2") (pinfunction "2_2") (pintype "passive"))
      (node (ref "X") (pin "5") (pinfunction "2Q_5") (pintype "output"))
      (node (ref "XB") (pin "3") (pinfunction "A2_3") (pintype "bidirectional"))
    )
    (net (code "237") (name "X2") (class "Default")
      (node (ref "RX-2") (pin "2") (pinfunction "2_2") (pintype "passive"))
      (node (ref "X") (pin "6") (pinfunction "3Q_6") (pintype "output"))
      (node (ref "XB") (pin "4") (pinfunction "A3_4") (pintype "bidirectional"))
    )
    (net (code "238") (name "X3") (class "Default")
      (node (ref "RX-3") (pin "2") (pinfunction "2_2") (pintype "passive"))
      (node (ref "X") (pin "9") (pinfunction "4Q_9") (pintype "output"))
      (node (ref "XB") (pin "5") (pinfunction "A4_5") (pintype "bidirectional"))
    )
    (net (code "239") (name "X4") (class "Default")
      (node (ref "RX-4") (pin "2") (pinfunction "2_2") (pintype "passive"))
      (node (ref "X") (pin "12") (pinfunction "5Q_12") (pintype "output"))
      (node (ref "XB") (pin "6") (pinfunction "A5_6") (pintype "bidirectional"))
    )
    (net (code "240") (name "X5") (class "Default")
      (node (ref "RX-5") (pin "2") (pinfunction "2_2") (pintype "passive"))
      (node (ref "X") (pin "15") (pinfunction "6Q_15") (pintype "output"))
      (node (ref "XB") (pin "7") (pinfunction "A6_7") (pintype "bidirectional"))
    )
    (net (code "241") (name "X6") (class "Default")
      (node (ref "RX-6") (pin "2") (pinfunction "2_2") (pintype "passive"))
      (node (ref "X") (pin "16") (pinfunction "7Q_16") (pintype "output"))
      (node (ref "XB") (pin "8") (pinfunction "A7_8") (pintype "bidirectional"))
    )
    (net (code "242") (name "X7") (class "Default")
      (node (ref "RX-7") (pin "2") (pinfunction "2_2") (pintype "passive"))
      (node (ref "X") (pin "19") (pinfunction "8Q_19") (pintype "output"))
      (node (ref "XB") (pin "9") (pinfunction "A8_9") (pintype "bidirectional"))
    )
    (net (code "243") (name "XO-B") (class "Default")
      (node (ref "XOB") (pin "19") (pinfunction "~{G}_19") (pintype "input"))
    )
    (net (code "244") (name "XO0") (class "Default")
      (node (ref "RXO-0") (pin "2") (pinfunction "2_2") (pintype "passive"))
      (node (ref "XOB") (pin "2") (pinfunction "A1_2") (pintype "bidirectional"))
      (node (ref "XOL") (pin "3") (pinfunction "Y_3") (pintype "output"))
    )
    (net (code "245") (name "XO1") (class "Default")
      (node (ref "RXO-1") (pin "2") (pinfunction "2_2") (pintype "passive"))
      (node (ref "XOB") (pin "3") (pinfunction "A2_3") (pintype "bidirectional"))
      (node (ref "XOL") (pin "6") (pinfunction "Y_6") (pintype "output"))
    )
    (net (code "246") (name "XO2") (class "Default")
      (node (ref "RXO-2") (pin "2") (pinfunction "2_2") (pintype "passive"))
      (node (ref "XOB") (pin "4") (pinfunction "A3_4") (pintype "bidirectional"))
      (node (ref "XOL") (pin "8") (pinfunction "Y_8") (pintype "output"))
    )
    (net (code "247") (name "XO3") (class "Default")
      (node (ref "RXO-3") (pin "2") (pinfunction "2_2") (pintype "passive"))
      (node (ref "XOB") (pin "5") (pinfunction "A4_5") (pintype "bidirectional"))
      (node (ref "XOL") (pin "11") (pinfunction "Y_11") (pintype "output"))
    )
    (net (code "248") (name "XO4") (class "Default")
      (node (ref "RXO-4") (pin "2") (pinfunction "2_2") (pintype "passive"))
      (node (ref "XOB") (pin "6") (pinfunction "A5_6") (pintype "bidirectional"))
      (node (ref "XOH") (pin "3") (pinfunction "Y_3") (pintype "output"))
    )
    (net (code "249") (name "XO5") (class "Default")
      (node (ref "RXO-5") (pin "2") (pinfunction "2_2") (pintype "passive"))
      (node (ref "XOB") (pin "7") (pinfunction "A6_7") (pintype "bidirectional"))
      (node (ref "XOH") (pin "6") (pinfunction "Y_6") (pintype "output"))
    )
    (net (code "250") (name "XO6") (class "Default")
      (node (ref "RXO-6") (pin "2") (pinfunction "2_2") (pintype "passive"))
      (node (ref "XOB") (pin "8") (pinfunction "A7_8") (pintype "bidirectional"))
      (node (ref "XOH") (pin "8") (pinfunction "Y_8") (pintype "output"))
    )
    (net (code "251") (name "XO7") (class "Default")
      (node (ref "RXO-7") (pin "2") (pinfunction "2_2") (pintype "passive"))
      (node (ref "XOB") (pin "9") (pinfunction "A8_9") (pintype "bidirectional"))
      (node (ref "XOH") (pin "11") (pinfunction "Y_11") (pintype "output"))
    )
    (net (code "252") (name "Y-B") (class "Default")
      (node (ref "YB") (pin "19") (pinfunction "~{G}_19") (pintype "input"))
    )
    (net (code "253") (name "Y-C") (class "Default")
      (node (ref "Y") (pin "11") (pinfunction "CLK_11") (pintype "input"))
    )
    (net (code "254") (name "Y0") (class "Default")
      (node (ref "RY-0") (pin "2") (pinfunction "2_2") (pintype "passive"))
      (node (ref "Y") (pin "2") (pinfunction "1Q_2") (pintype "output"))
      (node (ref "YB") (pin "2") (pinfunction "A1_2") (pintype "bidirectional"))
    )
    (net (code "255") (name "Y1") (class "Default")
      (node (ref "RY-1") (pin "2") (pinfunction "2_2") (pintype "passive"))
      (node (ref "Y") (pin "5") (pinfunction "2Q_5") (pintype "output"))
      (node (ref "YB") (pin "3") (pinfunction "A2_3") (pintype "bidirectional"))
    )
    (net (code "256") (name "Y2") (class "Default")
      (node (ref "RY-2") (pin "2") (pinfunction "2_2") (pintype "passive"))
      (node (ref "Y") (pin "6") (pinfunction "3Q_6") (pintype "output"))
      (node (ref "YB") (pin "4") (pinfunction "A3_4") (pintype "bidirectional"))
    )
    (net (code "257") (name "Y3") (class "Default")
      (node (ref "RY-3") (pin "2") (pinfunction "2_2") (pintype "passive"))
      (node (ref "Y") (pin "9") (pinfunction "4Q_9") (pintype "output"))
      (node (ref "YB") (pin "5") (pinfunction "A4_5") (pintype "bidirectional"))
    )
    (net (code "258") (name "Y4") (class "Default")
      (node (ref "RY-4") (pin "2") (pinfunction "2_2") (pintype "passive"))
      (node (ref "Y") (pin "12") (pinfunction "5Q_12") (pintype "output"))
      (node (ref "YB") (pin "6") (pinfunction "A5_6") (pintype "bidirectional"))
    )
    (net (code "259") (name "Y5") (class "Default")
      (node (ref "RY-5") (pin "2") (pinfunction "2_2") (pintype "passive"))
      (node (ref "Y") (pin "15") (pinfunction "6Q_15") (pintype "output"))
      (node (ref "YB") (pin "7") (pinfunction "A6_7") (pintype "bidirectional"))
    )
    (net (code "260") (name "Y6") (class "Default")
      (node (ref "RY-6") (pin "2") (pinfunction "2_2") (pintype "passive"))
      (node (ref "Y") (pin "16") (pinfunction "7Q_16") (pintype "output"))
      (node (ref "YB") (pin "8") (pinfunction "A7_8") (pintype "bidirectional"))
    )
    (net (code "261") (name "Y7") (class "Default")
      (node (ref "RY-7") (pin "2") (pinfunction "2_2") (pintype "passive"))
      (node (ref "Y") (pin "19") (pinfunction "8Q_19") (pintype "output"))
      (node (ref "YB") (pin "9") (pinfunction "A8_9") (pintype "bidirectional"))
    )
    (net (code "262") (name "ZF") (class "Default")
      (node (ref "ZH") (pin "8") (pinfunction "Y_8") (pintype "output"))
    )
    (net (code "263") (name "unconnected-(LX-8-C-PadK)") (class "Default")
      (node (ref "LX-8") (pin "K") (pinfunction "C_K") (pintype "passive"))
    )
    (net (code "264") (name "unconnected-(PC0C-~{BO}-Pad13)") (class "Default")
      (node (ref "PC0") (pin "13") (pinfunction "~{BO}_13") (pintype "output"))
    )
    (net (code "265") (name "unconnected-(PC1C-~{BO}-Pad13)") (class "Default")
      (node (ref "PC1") (pin "13") (pinfunction "~{BO}_13") (pintype "output"))
    )
    (net (code "266") (name "unconnected-(PC2C-~{BO}-Pad13)") (class "Default")
      (node (ref "PC2") (pin "13") (pinfunction "~{BO}_13") (pintype "output"))
    )
    (net (code "267") (name "unconnected-(PC3C-QC-Pad6)") (class "Default")
      (node (ref "PC3") (pin "6") (pinfunction "QC_6") (pintype "output"))
    )
    (net (code "268") (name "unconnected-(PC3C-QD-Pad7)") (class "Default")
      (node (ref "PC3") (pin "7") (pinfunction "QD_7") (pintype "output"))
    )
    (net (code "269") (name "unconnected-(PC3C-~{BO}-Pad13)") (class "Default")
      (node (ref "PC3") (pin "13") (pinfunction "~{BO}_13") (pintype "output"))
    )
    (net (code "270") (name "unconnected-(PC3C-~{CO}-Pad12)") (class "Default")
      (node (ref "PC3") (pin "12") (pinfunction "~{CO}_12") (pintype "output"))
    )
    (net (code "271") (name "unconnected-(PH-SC-A6-Pad7)") (class "Default")
      (node (ref "PH-S") (pin "7") (pinfunction "A6_7") (pintype "bidirectional"))
    )
    (net (code "272") (name "unconnected-(PH-SC-A7-Pad8)") (class "Default")
      (node (ref "PH-S") (pin "8") (pinfunction "A7_8") (pintype "bidirectional"))
    )
    (net (code "273") (name "unconnected-(PH-SC-A8-Pad9)") (class "Default")
      (node (ref "PH-S") (pin "9") (pinfunction "A8_9") (pintype "bidirectional"))
    )
    (net (code "274") (name "unconnected-(PH-SC-B6-Pad13)") (class "Default")
      (node (ref "PH-S") (pin "13") (pinfunction "B6_13") (pintype "bidirectional"))
    )
    (net (code "275") (name "unconnected-(PH-SC-B7-Pad12)") (class "Default")
      (node (ref "PH-S") (pin "12") (pinfunction "B7_12") (pintype "bidirectional"))
    )
    (net (code "276") (name "unconnected-(PH-SC-B8-Pad11)") (class "Default")
      (node (ref "PH-S") (pin "11") (pinfunction "B8_11") (pintype "bidirectional"))
    )
    (net (code "277") (name "unconnected-(PR-HC-6D-Pad14)") (class "Default")
      (node (ref "PR-H") (pin "14") (pinfunction "6D_14") (pintype "input"))
    )
    (net (code "278") (name "unconnected-(PR-HC-6Q-Pad15)") (class "Default")
      (node (ref "PR-H") (pin "15") (pinfunction "6Q_15") (pintype "output"))
    )
    (net (code "279") (name "unconnected-(PR-HC-7D-Pad17)") (class "Default")
      (node (ref "PR-H") (pin "17") (pinfunction "7D_17") (pintype "input"))
    )
    (net (code "280") (name "unconnected-(PR-HC-7Q-Pad16)") (class "Default")
      (node (ref "PR-H") (pin "16") (pinfunction "7Q_16") (pintype "output"))
    )
    (net (code "281") (name "unconnected-(PR-HC-8D-Pad18)") (class "Default")
      (node (ref "PR-H") (pin "18") (pinfunction "8D_18") (pintype "input"))
    )
    (net (code "282") (name "unconnected-(PR-HC-8Q-Pad19)") (class "Default")
      (node (ref "PR-H") (pin "19") (pinfunction "8Q_19") (pintype "output"))
    )
    (net (code "283") (name "unconnected-(ROM-NC-Pad1)") (class "Default")
      (node (ref "ROM") (pin "1") (pinfunction "NC_1") (pintype "no_connect"))
    )
    (net (code "284") (name "unconnected-(ROM-NC-Pad26)") (class "Default")
      (node (ref "ROM") (pin "26") (pinfunction "NC_26") (pintype "no_connect"))
    )
  )
)
